# dig_usb.net
KiCad netlist of a schematic drawn in EAGLE
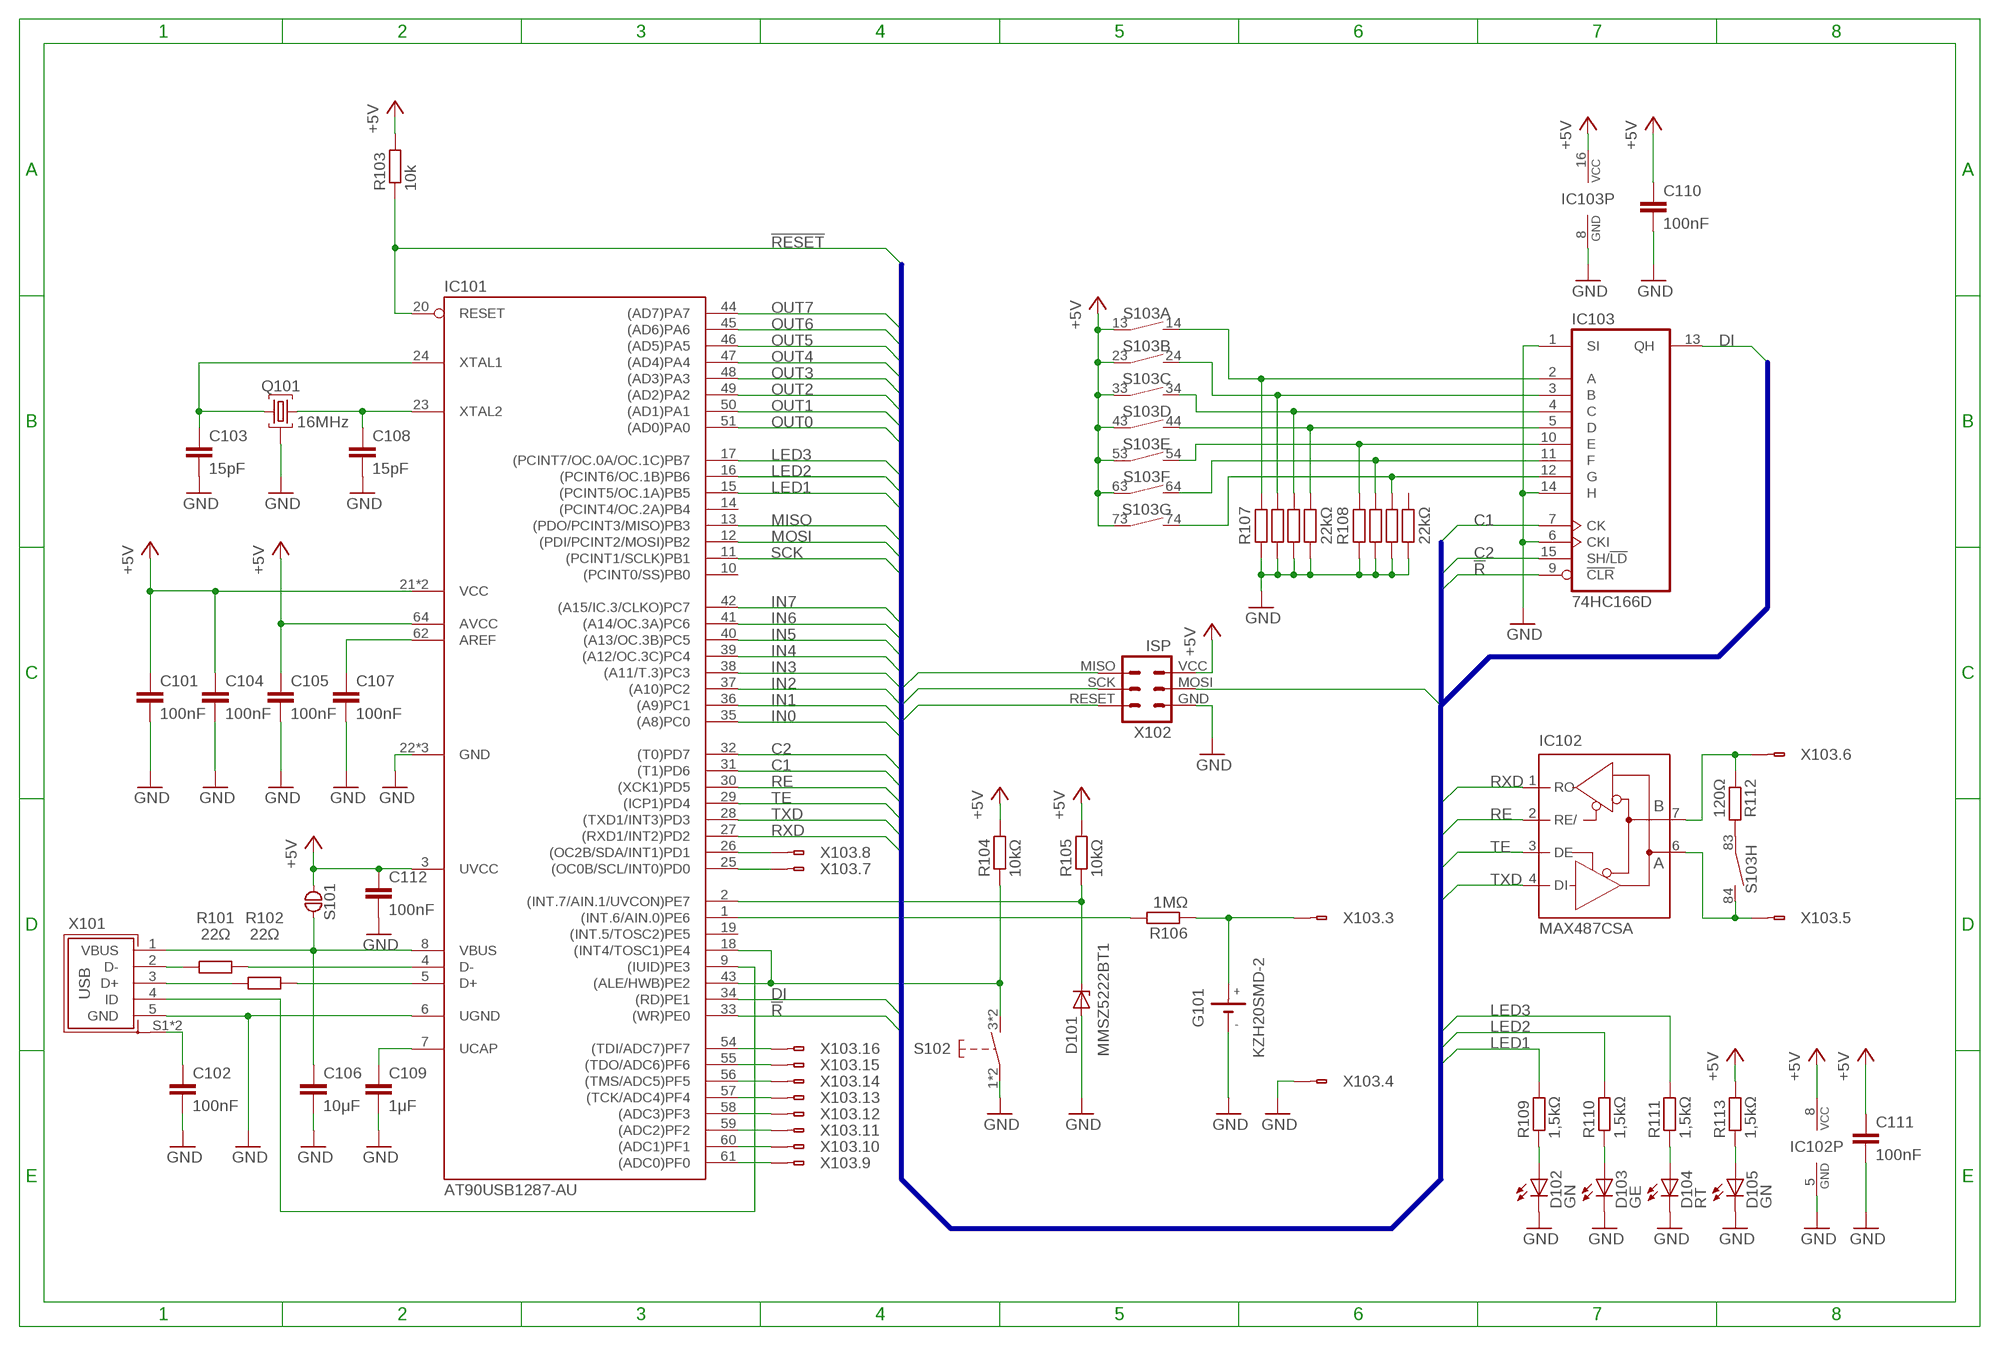
[diagram p0: schematic, sheet 1]
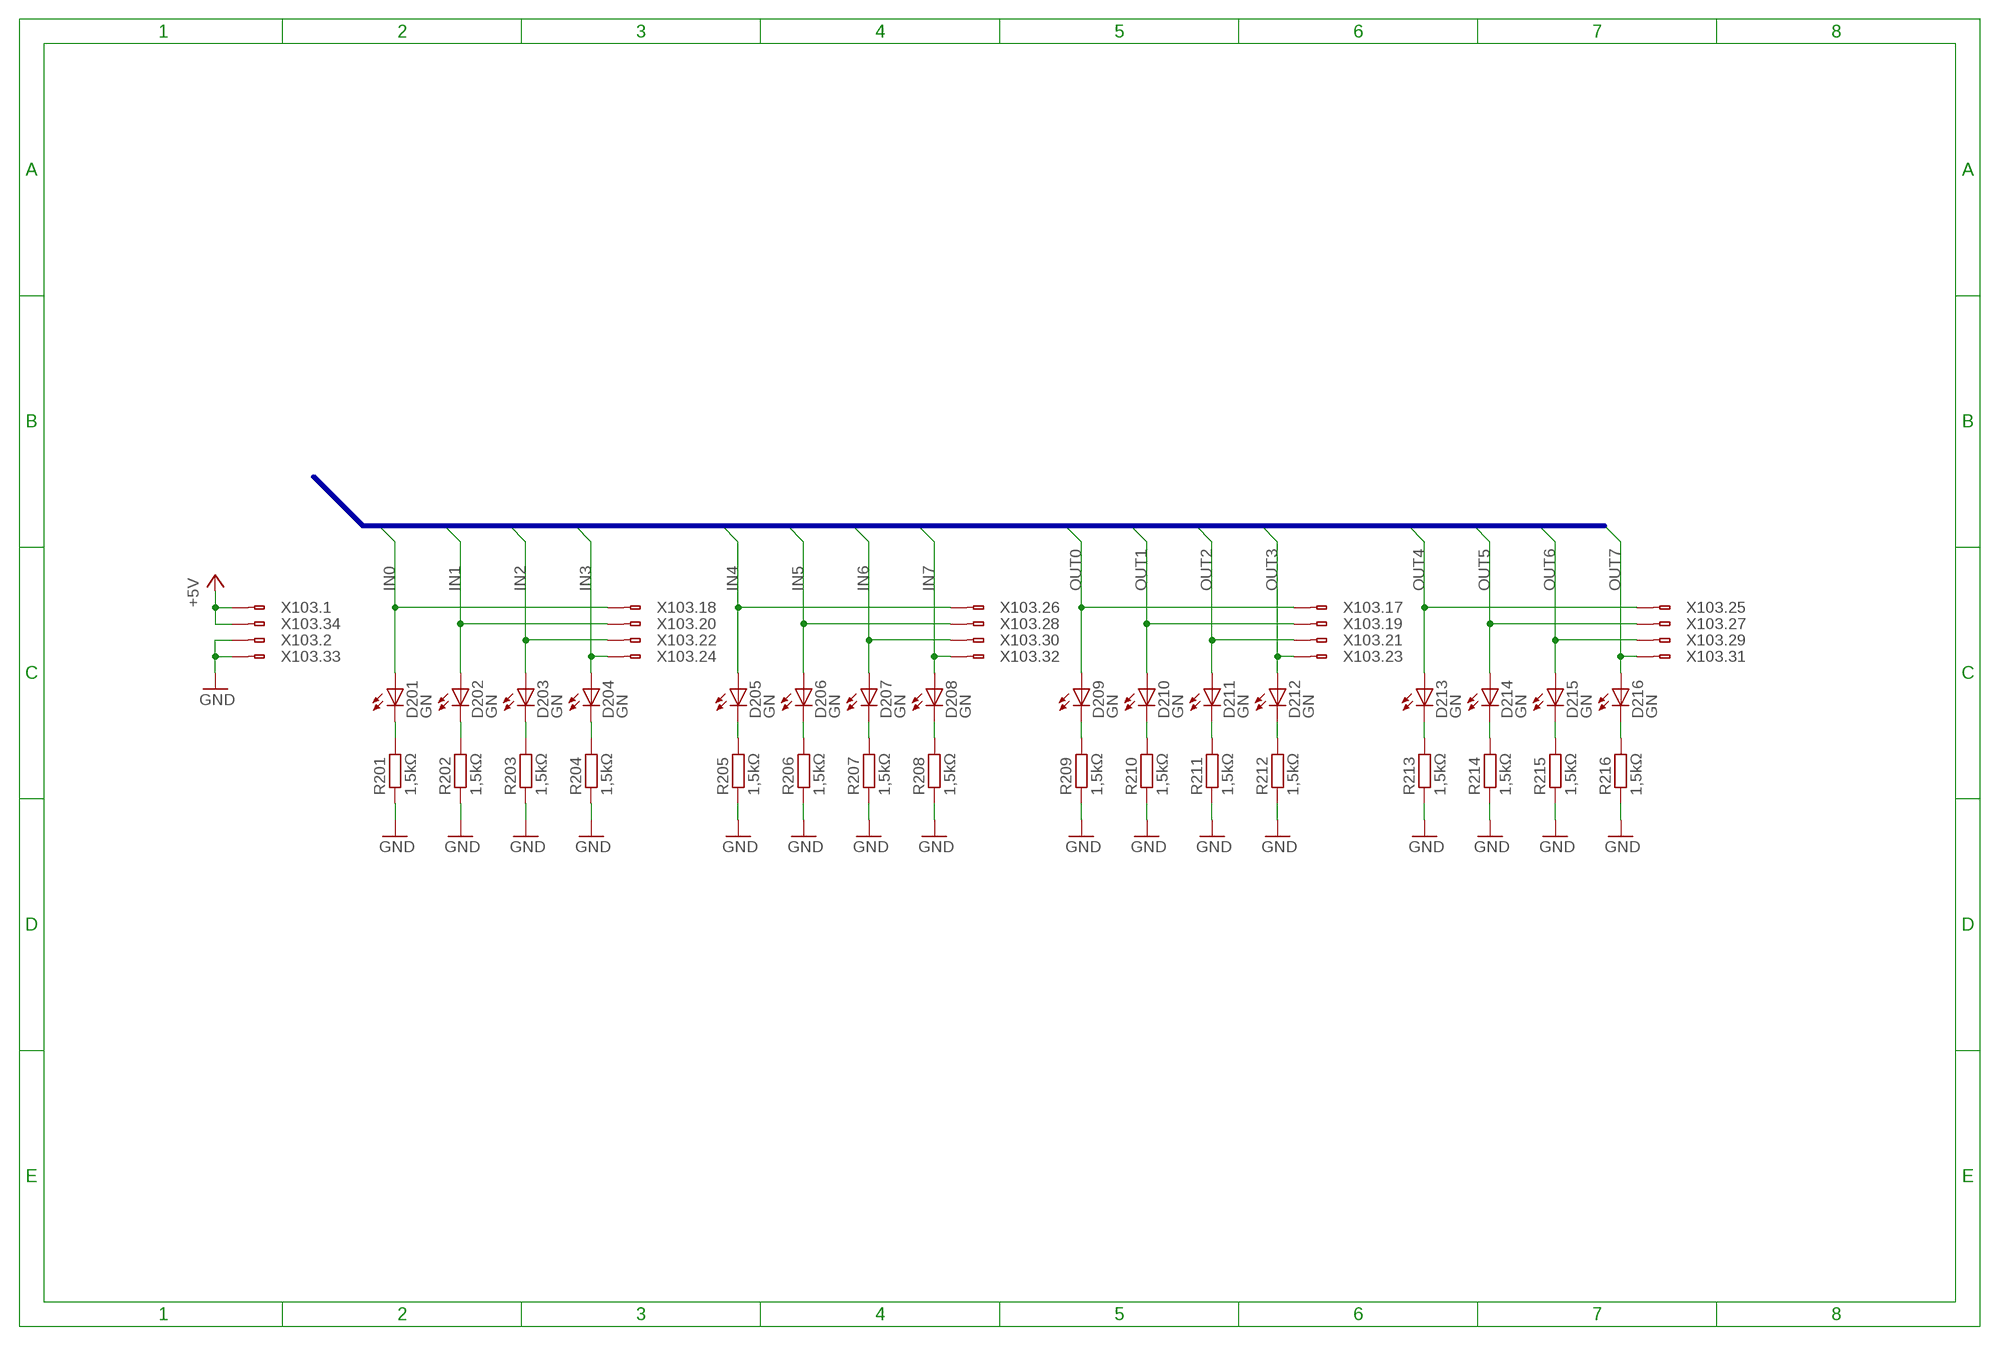
[diagram p1: schematic, sheet 2]
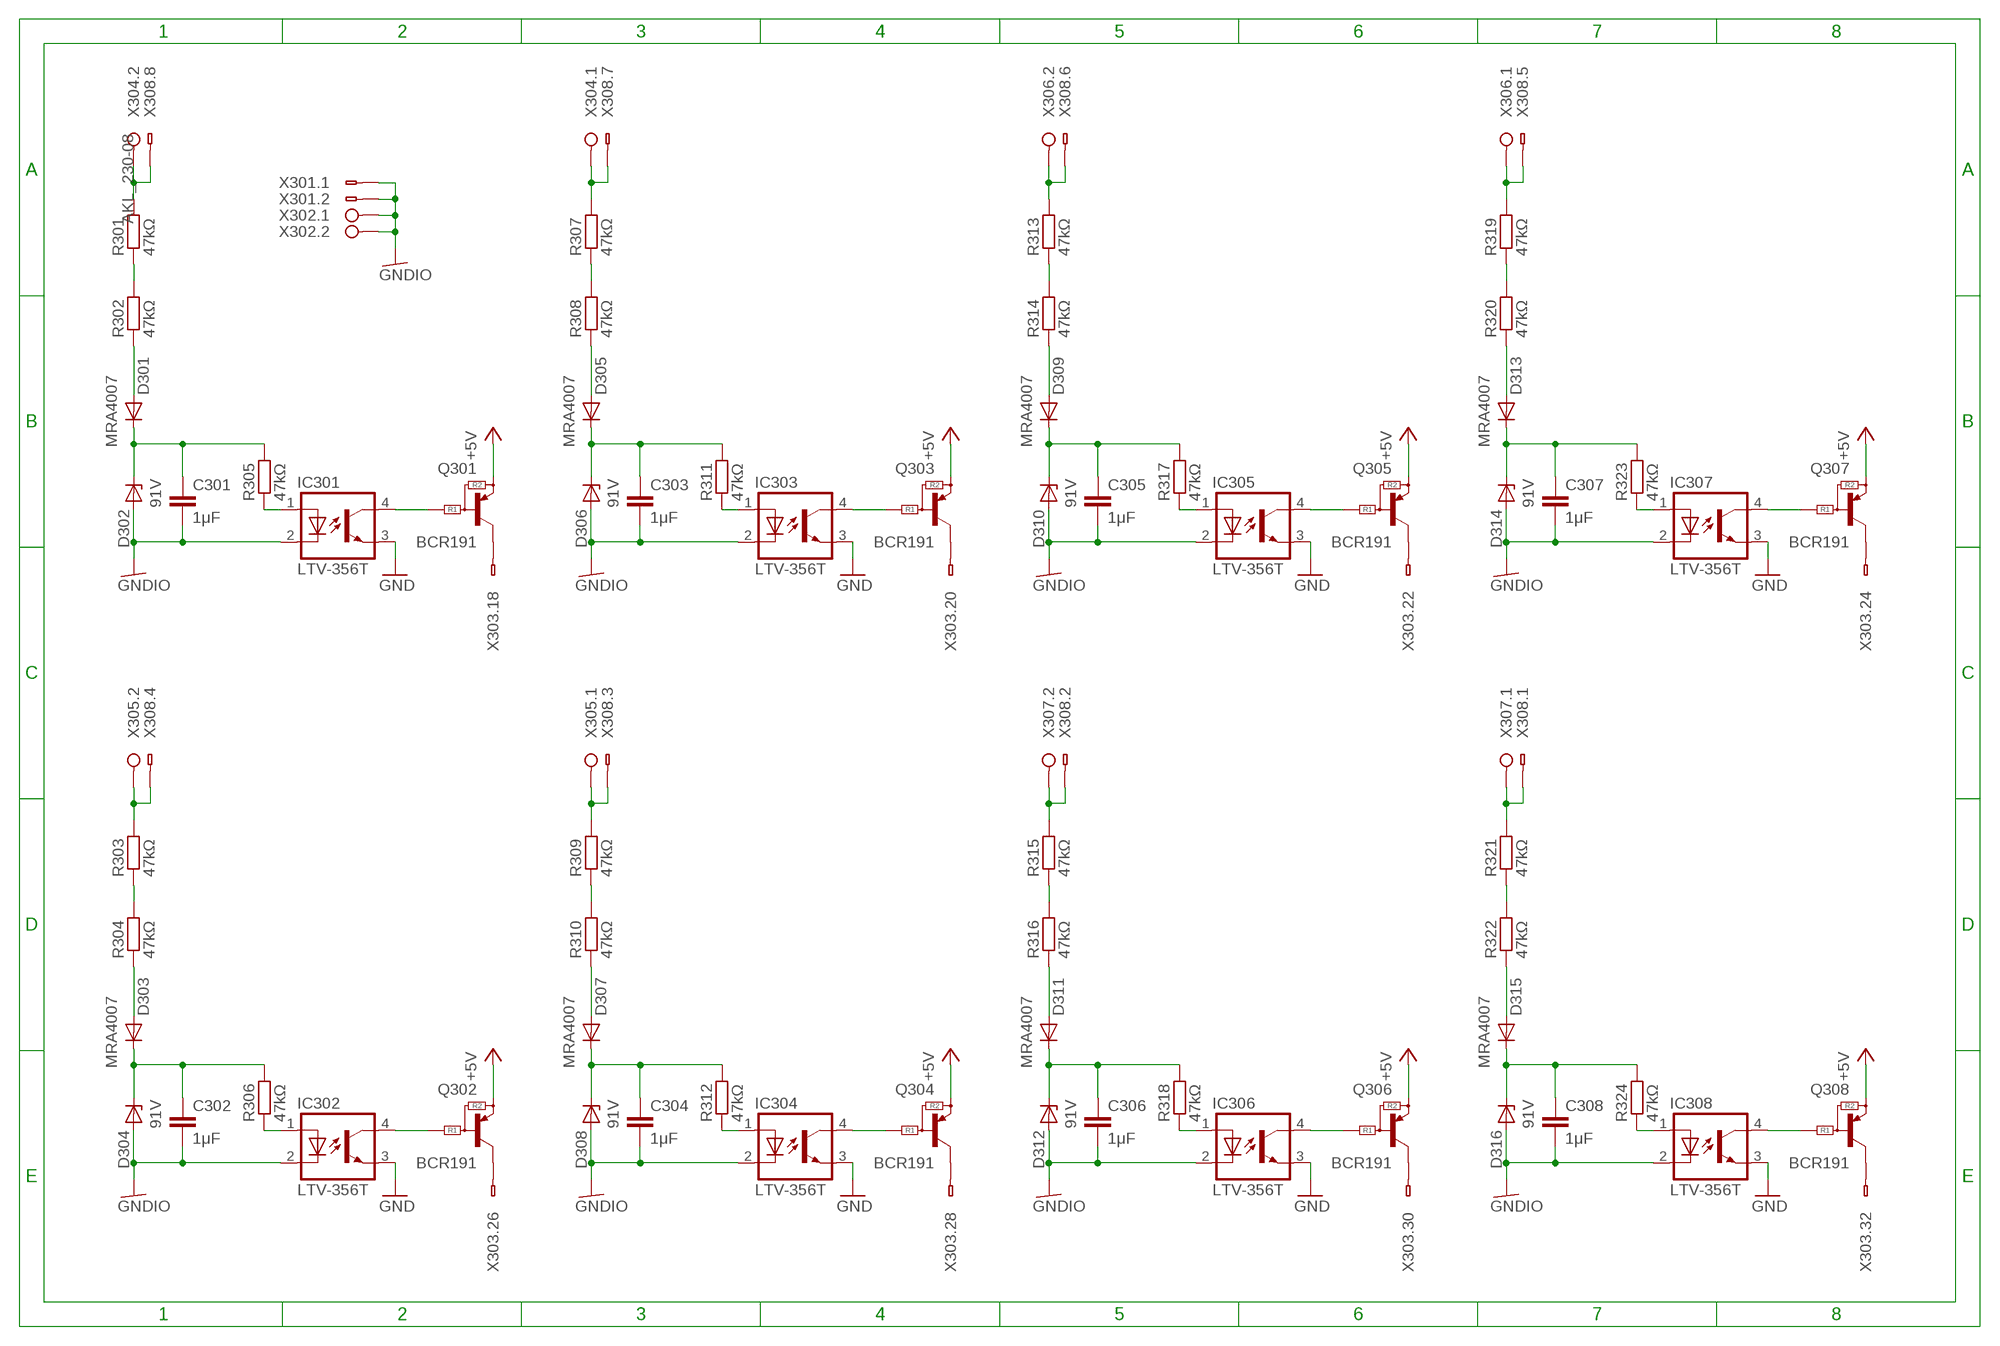
[diagram p2: schematic, sheet 3]
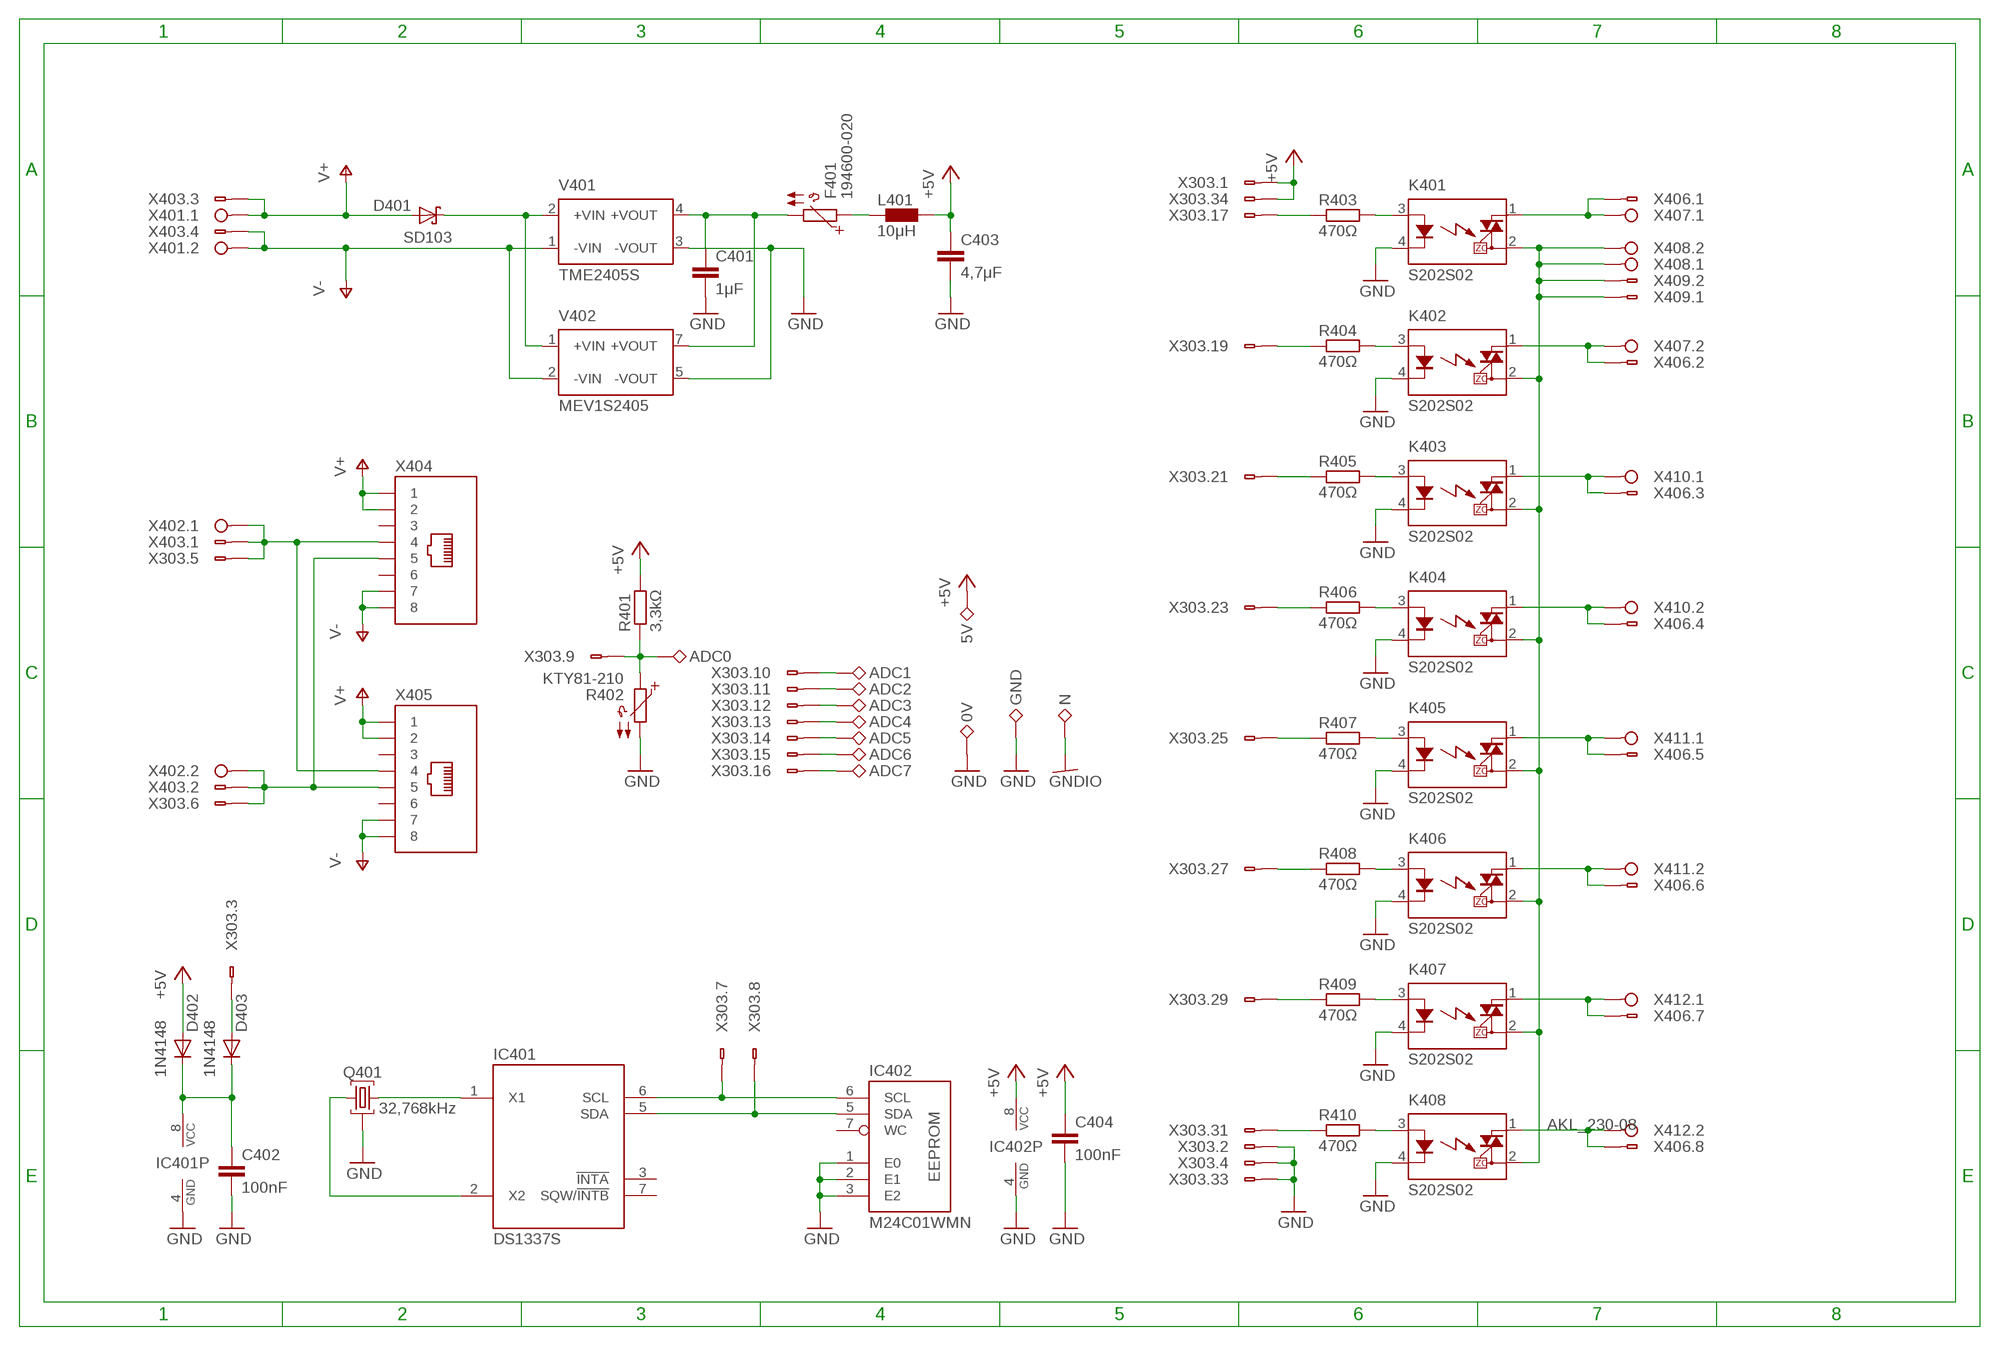
[diagram p3: schematic, sheet 4]

(export (version "E")
  (design (tool "Eeschema 10.0.6"))
  (components
    (comp (ref "C301")
      (value "1μF")
      (footprint "eagle-import:CHIP_1206")
      (libsource (lib "eagle-import") (part "C_1206"))
    )
    (comp (ref "C302")
      (value "1μF")
      (footprint "eagle-import:CHIP_1206")
      (libsource (lib "eagle-import") (part "C_1206"))
    )
    (comp (ref "C303")
      (value "1μF")
      (footprint "eagle-import:CHIP_1206")
      (libsource (lib "eagle-import") (part "C_1206"))
    )
    (comp (ref "C304")
      (value "1μF")
      (footprint "eagle-import:CHIP_1206")
      (libsource (lib "eagle-import") (part "C_1206"))
    )
    (comp (ref "C305")
      (value "1μF")
      (footprint "eagle-import:CHIP_1206")
      (libsource (lib "eagle-import") (part "C_1206"))
    )
    (comp (ref "C306")
      (value "1μF")
      (footprint "eagle-import:CHIP_1206")
      (libsource (lib "eagle-import") (part "C_1206"))
    )
    (comp (ref "C307")
      (value "1μF")
      (footprint "eagle-import:CHIP_1206")
      (libsource (lib "eagle-import") (part "C_1206"))
    )
    (comp (ref "C308")
      (value "1μF")
      (footprint "eagle-import:CHIP_1206")
      (libsource (lib "eagle-import") (part "C_1206"))
    )
    (comp (ref "D301")
      (value "MRA4007")
      (footprint "eagle-import:DO214AC")
      (libsource (lib "eagle-import") (part "DIODE-DO214AC"))
    )
    (comp (ref "D302")
      (value "91V")
      (footprint "eagle-import:SOD123")
      (libsource (lib "eagle-import") (part "Z-DIODE-SOD123"))
    )
    (comp (ref "D303")
      (value "MRA4007")
      (footprint "eagle-import:DO214AC")
      (libsource (lib "eagle-import") (part "DIODE-DO214AC"))
    )
    (comp (ref "D304")
      (value "91V")
      (footprint "eagle-import:SOD123")
      (libsource (lib "eagle-import") (part "Z-DIODE-SOD123"))
    )
    (comp (ref "D305")
      (value "MRA4007")
      (footprint "eagle-import:DO214AC")
      (libsource (lib "eagle-import") (part "DIODE-DO214AC"))
    )
    (comp (ref "D306")
      (value "91V")
      (footprint "eagle-import:SOD123")
      (libsource (lib "eagle-import") (part "Z-DIODE-SOD123"))
    )
    (comp (ref "D307")
      (value "MRA4007")
      (footprint "eagle-import:DO214AC")
      (libsource (lib "eagle-import") (part "DIODE-DO214AC"))
    )
    (comp (ref "D308")
      (value "91V")
      (footprint "eagle-import:SOD123")
      (libsource (lib "eagle-import") (part "Z-DIODE-SOD123"))
    )
    (comp (ref "D309")
      (value "MRA4007")
      (footprint "eagle-import:DO214AC")
      (libsource (lib "eagle-import") (part "DIODE-DO214AC"))
    )
    (comp (ref "D310")
      (value "91V")
      (footprint "eagle-import:SOD123")
      (libsource (lib "eagle-import") (part "Z-DIODE-SOD123"))
    )
    (comp (ref "D311")
      (value "MRA4007")
      (footprint "eagle-import:DO214AC")
      (libsource (lib "eagle-import") (part "DIODE-DO214AC"))
    )
    (comp (ref "D312")
      (value "91V")
      (footprint "eagle-import:SOD123")
      (libsource (lib "eagle-import") (part "Z-DIODE-SOD123"))
    )
    (comp (ref "D313")
      (value "MRA4007")
      (footprint "eagle-import:DO214AC")
      (libsource (lib "eagle-import") (part "DIODE-DO214AC"))
    )
    (comp (ref "D314")
      (value "91V")
      (footprint "eagle-import:SOD123")
      (libsource (lib "eagle-import") (part "Z-DIODE-SOD123"))
    )
    (comp (ref "D315")
      (value "MRA4007")
      (footprint "eagle-import:DO214AC")
      (libsource (lib "eagle-import") (part "DIODE-DO214AC"))
    )
    (comp (ref "D316")
      (value "91V")
      (footprint "eagle-import:SOD123")
      (libsource (lib "eagle-import") (part "Z-DIODE-SOD123"))
    )
    (comp (ref "IC301")
      (value "LTV-356T")
      (footprint "eagle-import:SOP04_254")
      (libsource (lib "eagle-import") (part "LTV-356T"))
    )
    (comp (ref "IC302")
      (value "LTV-356T")
      (footprint "eagle-import:SOP04_254")
      (libsource (lib "eagle-import") (part "LTV-356T"))
    )
    (comp (ref "IC303")
      (value "LTV-356T")
      (footprint "eagle-import:SOP04_254")
      (libsource (lib "eagle-import") (part "LTV-356T"))
    )
    (comp (ref "IC304")
      (value "LTV-356T")
      (footprint "eagle-import:SOP04_254")
      (libsource (lib "eagle-import") (part "LTV-356T"))
    )
    (comp (ref "IC305")
      (value "LTV-356T")
      (footprint "eagle-import:SOP04_254")
      (libsource (lib "eagle-import") (part "LTV-356T"))
    )
    (comp (ref "IC306")
      (value "LTV-356T")
      (footprint "eagle-import:SOP04_254")
      (libsource (lib "eagle-import") (part "LTV-356T"))
    )
    (comp (ref "IC307")
      (value "LTV-356T")
      (footprint "eagle-import:SOP04_254")
      (libsource (lib "eagle-import") (part "LTV-356T"))
    )
    (comp (ref "IC308")
      (value "LTV-356T")
      (footprint "eagle-import:SOP04_254")
      (libsource (lib "eagle-import") (part "LTV-356T"))
    )
    (comp (ref "Q301")
      (value "BCR191")
      (footprint "eagle-import:SOT23")
      (libsource (lib "eagle-import") (part "PNP2R-SOT23-BEC"))
    )
    (comp (ref "Q302")
      (value "BCR191")
      (footprint "eagle-import:SOT23")
      (libsource (lib "eagle-import") (part "PNP2R-SOT23-BEC"))
    )
    (comp (ref "Q303")
      (value "BCR191")
      (footprint "eagle-import:SOT23")
      (libsource (lib "eagle-import") (part "PNP2R-SOT23-BEC"))
    )
    (comp (ref "Q304")
      (value "BCR191")
      (footprint "eagle-import:SOT23")
      (libsource (lib "eagle-import") (part "PNP2R-SOT23-BEC"))
    )
    (comp (ref "Q305")
      (value "BCR191")
      (footprint "eagle-import:SOT23")
      (libsource (lib "eagle-import") (part "PNP2R-SOT23-BEC"))
    )
    (comp (ref "Q306")
      (value "BCR191")
      (footprint "eagle-import:SOT23")
      (libsource (lib "eagle-import") (part "PNP2R-SOT23-BEC"))
    )
    (comp (ref "Q307")
      (value "BCR191")
      (footprint "eagle-import:SOT23")
      (libsource (lib "eagle-import") (part "PNP2R-SOT23-BEC"))
    )
    (comp (ref "Q308")
      (value "BCR191")
      (footprint "eagle-import:SOT23")
      (libsource (lib "eagle-import") (part "PNP2R-SOT23-BEC"))
    )
    (comp (ref "R301")
      (value "47kΩ")
      (footprint "eagle-import:CHIP_1206")
      (libsource (lib "eagle-import") (part "R_1206"))
    )
    (comp (ref "R302")
      (value "47kΩ")
      (footprint "eagle-import:CHIP_1206")
      (libsource (lib "eagle-import") (part "R_1206"))
    )
    (comp (ref "R303")
      (value "47kΩ")
      (footprint "eagle-import:CHIP_1206")
      (libsource (lib "eagle-import") (part "R_1206"))
    )
    (comp (ref "R304")
      (value "47kΩ")
      (footprint "eagle-import:CHIP_1206")
      (libsource (lib "eagle-import") (part "R_1206"))
    )
    (comp (ref "R305")
      (value "47kΩ")
      (footprint "eagle-import:CHIP_1206")
      (libsource (lib "eagle-import") (part "R_1206"))
    )
    (comp (ref "R306")
      (value "47kΩ")
      (footprint "eagle-import:CHIP_1206")
      (libsource (lib "eagle-import") (part "R_1206"))
    )
    (comp (ref "R307")
      (value "47kΩ")
      (footprint "eagle-import:CHIP_1206")
      (libsource (lib "eagle-import") (part "R_1206"))
    )
    (comp (ref "R308")
      (value "47kΩ")
      (footprint "eagle-import:CHIP_1206")
      (libsource (lib "eagle-import") (part "R_1206"))
    )
    (comp (ref "R309")
      (value "47kΩ")
      (footprint "eagle-import:CHIP_1206")
      (libsource (lib "eagle-import") (part "R_1206"))
    )
    (comp (ref "R310")
      (value "47kΩ")
      (footprint "eagle-import:CHIP_1206")
      (libsource (lib "eagle-import") (part "R_1206"))
    )
    (comp (ref "R311")
      (value "47kΩ")
      (footprint "eagle-import:CHIP_1206")
      (libsource (lib "eagle-import") (part "R_1206"))
    )
    (comp (ref "R312")
      (value "47kΩ")
      (footprint "eagle-import:CHIP_1206")
      (libsource (lib "eagle-import") (part "R_1206"))
    )
    (comp (ref "R313")
      (value "47kΩ")
      (footprint "eagle-import:CHIP_1206")
      (libsource (lib "eagle-import") (part "R_1206"))
    )
    (comp (ref "R314")
      (value "47kΩ")
      (footprint "eagle-import:CHIP_1206")
      (libsource (lib "eagle-import") (part "R_1206"))
    )
    (comp (ref "R315")
      (value "47kΩ")
      (footprint "eagle-import:CHIP_1206")
      (libsource (lib "eagle-import") (part "R_1206"))
    )
    (comp (ref "R316")
      (value "47kΩ")
      (footprint "eagle-import:CHIP_1206")
      (libsource (lib "eagle-import") (part "R_1206"))
    )
    (comp (ref "R317")
      (value "47kΩ")
      (footprint "eagle-import:CHIP_1206")
      (libsource (lib "eagle-import") (part "R_1206"))
    )
    (comp (ref "R318")
      (value "47kΩ")
      (footprint "eagle-import:CHIP_1206")
      (libsource (lib "eagle-import") (part "R_1206"))
    )
    (comp (ref "R319")
      (value "47kΩ")
      (footprint "eagle-import:CHIP_1206")
      (libsource (lib "eagle-import") (part "R_1206"))
    )
    (comp (ref "R320")
      (value "47kΩ")
      (footprint "eagle-import:CHIP_1206")
      (libsource (lib "eagle-import") (part "R_1206"))
    )
    (comp (ref "R321")
      (value "47kΩ")
      (footprint "eagle-import:CHIP_1206")
      (libsource (lib "eagle-import") (part "R_1206"))
    )
    (comp (ref "R322")
      (value "47kΩ")
      (footprint "eagle-import:CHIP_1206")
      (libsource (lib "eagle-import") (part "R_1206"))
    )
    (comp (ref "R323")
      (value "47kΩ")
      (footprint "eagle-import:CHIP_1206")
      (libsource (lib "eagle-import") (part "R_1206"))
    )
    (comp (ref "R324")
      (value "47kΩ")
      (footprint "eagle-import:CHIP_1206")
      (libsource (lib "eagle-import") (part "R_1206"))
    )
    (comp (ref "X301")
      (value "AKL_230-02")
      (footprint "eagle-import:AKL_230-02")
      (libsource (lib "eagle-import") (part "AKL_230-02"))
    )
    (comp (ref "X302")
      (value "RIA-73-02")
      (footprint "eagle-import:RIA-73-02")
      (libsource (lib "eagle-import") (part "RIA-73-02"))
    )
    (comp (ref "X303")
      (value "WS34V")
      (footprint "eagle-import:WS34V")
      (libsource (lib "eagle-import") (part "WS34V"))
    )
    (comp (ref "X304")
      (value "RIA-73-02")
      (footprint "eagle-import:RIA-73-02")
      (libsource (lib "eagle-import") (part "RIA-73-02"))
    )
    (comp (ref "X305")
      (value "RIA-73-02")
      (footprint "eagle-import:RIA-73-02")
      (libsource (lib "eagle-import") (part "RIA-73-02"))
    )
    (comp (ref "X306")
      (value "RIA-73-02")
      (footprint "eagle-import:RIA-73-02")
      (libsource (lib "eagle-import") (part "RIA-73-02"))
    )
    (comp (ref "X307")
      (value "RIA-73-02")
      (footprint "eagle-import:RIA-73-02")
      (libsource (lib "eagle-import") (part "RIA-73-02"))
    )
    (comp (ref "X308")
      (value "AKL_230-08")
      (footprint "eagle-import:AKL_230-08")
      (libsource (lib "eagle-import") (part "AKL_230-08"))
    )
    (comp (ref "C101")
      (value "100nF")
      (footprint "eagle-import:CHIP_0603")
      (libsource (lib "eagle-import") (part "C_0603"))
    )
    (comp (ref "C102")
      (value "100nF")
      (footprint "eagle-import:CHIP_0805")
      (libsource (lib "eagle-import") (part "C_0805"))
    )
    (comp (ref "C103")
      (value "15pF")
      (footprint "eagle-import:CHIP_0805")
      (libsource (lib "eagle-import") (part "C_0805"))
    )
    (comp (ref "C104")
      (value "100nF")
      (footprint "eagle-import:CHIP_0603")
      (libsource (lib "eagle-import") (part "C_0603"))
    )
    (comp (ref "C105")
      (value "100nF")
      (footprint "eagle-import:CHIP_0603")
      (libsource (lib "eagle-import") (part "C_0603"))
    )
    (comp (ref "C106")
      (value "10μF")
      (footprint "eagle-import:CHIP_0805")
      (libsource (lib "eagle-import") (part "C_0805"))
    )
    (comp (ref "C107")
      (value "100nF")
      (footprint "eagle-import:CHIP_0603")
      (libsource (lib "eagle-import") (part "C_0603"))
    )
    (comp (ref "C108")
      (value "15pF")
      (footprint "eagle-import:CHIP_0805")
      (libsource (lib "eagle-import") (part "C_0805"))
    )
    (comp (ref "C109")
      (value "1μF")
      (footprint "eagle-import:CHIP_0805")
      (libsource (lib "eagle-import") (part "C_0805"))
    )
    (comp (ref "C110")
      (value "100nF")
      (footprint "eagle-import:CHIP_0603")
      (libsource (lib "eagle-import") (part "C_0603"))
    )
    (comp (ref "C111")
      (value "100nF")
      (footprint "eagle-import:CHIP_0603")
      (libsource (lib "eagle-import") (part "C_0603"))
    )
    (comp (ref "C112")
      (value "100nF")
      (footprint "eagle-import:CHIP_0603")
      (libsource (lib "eagle-import") (part "C_0603"))
    )
    (comp (ref "D101")
      (value "MMSZ5222BT1")
      (footprint "eagle-import:SOD123")
      (libsource (lib "eagle-import") (part "Z-DIODE-SOD123"))
    )
    (comp (ref "D102")
      (value "GN")
      (footprint "eagle-import:CHIP_0805")
      (libsource (lib "eagle-import") (part "LED_0805"))
    )
    (comp (ref "D103")
      (value "GE")
      (footprint "eagle-import:CHIP_0805")
      (libsource (lib "eagle-import") (part "LED_0805"))
    )
    (comp (ref "D104")
      (value "RT")
      (footprint "eagle-import:CHIP_0805")
      (libsource (lib "eagle-import") (part "LED_0805"))
    )
    (comp (ref "D105")
      (value "GN")
      (footprint "eagle-import:CHIP_0805")
      (libsource (lib "eagle-import") (part "LED_0805"))
    )
    (comp (ref "G101")
      (value "KZH20SMD-2")
      (footprint "eagle-import:KHZ20SMD-2")
      (libsource (lib "eagle-import") (part "KZH20SMD-2"))
    )
    (comp (ref "IC101")
      (value "AT90USB1287-AU")
      (footprint "eagle-import:QFP64_08")
      (libsource (lib "eagle-import") (part "AT90USB1287-AU"))
    )
    (comp (ref "IC102")
      (value "MAX487CSA")
      (footprint "eagle-import:SOP08_127")
      (libsource (lib "eagle-import") (part "MAX48CSA7"))
    )
    (comp (ref "IC103")
      (value "74HC166D")
      (footprint "eagle-import:SOP16_127")
      (libsource (lib "eagle-import") (part "74166DHC"))
    )
    (comp (ref "Q101")
      (value "16MHz")
      (footprint "eagle-import:X22")
      (libsource (lib "eagle-import") (part "QM_X22"))
    )
    (comp (ref "R101")
      (value "22Ω")
      (footprint "eagle-import:CHIP_0805")
      (libsource (lib "eagle-import") (part "R_0805"))
    )
    (comp (ref "R102")
      (value "22Ω")
      (footprint "eagle-import:CHIP_0805")
      (libsource (lib "eagle-import") (part "R_0805"))
    )
    (comp (ref "R103")
      (value "10k")
      (footprint "eagle-import:CHIP_0805")
      (libsource (lib "eagle-import") (part "R_0805"))
    )
    (comp (ref "R104")
      (value "10kΩ")
      (footprint "eagle-import:CHIP_0805")
      (libsource (lib "eagle-import") (part "R_0805"))
    )
    (comp (ref "R105")
      (value "10kΩ")
      (footprint "eagle-import:CHIP_0805")
      (libsource (lib "eagle-import") (part "R_0805"))
    )
    (comp (ref "R106")
      (value "1MΩ")
      (footprint "eagle-import:CHIP_0805")
      (libsource (lib "eagle-import") (part "R_0805"))
    )
    (comp (ref "R107")
      (value "22kΩ")
      (footprint "eagle-import:1206")
      (libsource (lib "eagle-import") (part "EXB-38V"))
    )
    (comp (ref "R108")
      (value "22kΩ")
      (footprint "eagle-import:1206")
      (libsource (lib "eagle-import") (part "EXB-38V"))
    )
    (comp (ref "R109")
      (value "1,5kΩ")
      (footprint "eagle-import:CHIP_0805")
      (libsource (lib "eagle-import") (part "R_0805"))
    )
    (comp (ref "R110")
      (value "1,5kΩ")
      (footprint "eagle-import:CHIP_0805")
      (libsource (lib "eagle-import") (part "R_0805"))
    )
    (comp (ref "R111")
      (value "1,5kΩ")
      (footprint "eagle-import:CHIP_0805")
      (libsource (lib "eagle-import") (part "R_0805"))
    )
    (comp (ref "R112")
      (value "120Ω")
      (footprint "eagle-import:CHIP_0805")
      (libsource (lib "eagle-import") (part "R_0805"))
    )
    (comp (ref "R113")
      (value "1,5kΩ")
      (footprint "eagle-import:CHIP_0805")
      (libsource (lib "eagle-import") (part "R_0805"))
    )
    (comp (ref "S101")
      (value "JUMPER")
      (footprint "eagle-import:JUMPER2")
      (libsource (lib "eagle-import") (part "JUMPER"))
    )
    (comp (ref "S102")
      (value "KURZHUBS1")
      (footprint "eagle-import:SCHURTER1301")
      (libsource (lib "eagle-import") (part "KURZHUBS1"))
    )
    (comp (ref "S103")
      (value "DP08D")
      (footprint "eagle-import:DIP08_SMD")
      (libsource (lib "eagle-import") (part "DP08D"))
    )
    (comp (ref "X101")
      (value "USB-MINI-V")
      (footprint "eagle-import:WE651005136421")
      (libsource (lib "eagle-import") (part "USB-MINI-V"))
    )
    (comp (ref "X102")
      (value "ISP")
      (footprint "eagle-import:ML6")
      (libsource (lib "eagle-import") (part "AVR_ISP6"))
    )
    (comp (ref "X103")
      (value "WS34V")
      (footprint "eagle-import:WS34V")
      (libsource (lib "eagle-import") (part "WS34V"))
    )
    (comp (ref "0V")
      (value "TEST_VIA_08")
      (footprint "eagle-import:VIA08")
      (libsource (lib "eagle-import") (part "TEST_VIA_08"))
    )
    (comp (ref "5V")
      (value "TEST_VIA_08")
      (footprint "eagle-import:VIA08")
      (libsource (lib "eagle-import") (part "TEST_VIA_08"))
    )
    (comp (ref "ADC0")
      (value "TEST_PAD_SMALL")
      (footprint "eagle-import:PADS")
      (libsource (lib "eagle-import") (part "TEST_PAD_SMALL"))
    )
    (comp (ref "ADC1")
      (value "TEST_PAD_SMALL")
      (footprint "eagle-import:PADS")
      (libsource (lib "eagle-import") (part "TEST_PAD_SMALL"))
    )
    (comp (ref "ADC2")
      (value "TEST_PAD_SMALL")
      (footprint "eagle-import:PADS")
      (libsource (lib "eagle-import") (part "TEST_PAD_SMALL"))
    )
    (comp (ref "ADC3")
      (value "TEST_PAD_SMALL")
      (footprint "eagle-import:PADS")
      (libsource (lib "eagle-import") (part "TEST_PAD_SMALL"))
    )
    (comp (ref "ADC4")
      (value "TEST_PAD_SMALL")
      (footprint "eagle-import:PADS")
      (libsource (lib "eagle-import") (part "TEST_PAD_SMALL"))
    )
    (comp (ref "ADC5")
      (value "TEST_PAD_SMALL")
      (footprint "eagle-import:PADS")
      (libsource (lib "eagle-import") (part "TEST_PAD_SMALL"))
    )
    (comp (ref "ADC6")
      (value "TEST_PAD_SMALL")
      (footprint "eagle-import:PADS")
      (libsource (lib "eagle-import") (part "TEST_PAD_SMALL"))
    )
    (comp (ref "ADC7")
      (value "TEST_PAD_SMALL")
      (footprint "eagle-import:PADS")
      (libsource (lib "eagle-import") (part "TEST_PAD_SMALL"))
    )
    (comp (ref "C401")
      (value "1μF")
      (footprint "eagle-import:CHIP_0805")
      (libsource (lib "eagle-import") (part "C_0805"))
    )
    (comp (ref "C402")
      (value "100nF")
      (footprint "eagle-import:CHIP_0603")
      (libsource (lib "eagle-import") (part "C_0603"))
    )
    (comp (ref "C403")
      (value "4,7μF")
      (footprint "eagle-import:CHIP_0805")
      (libsource (lib "eagle-import") (part "C_0805"))
    )
    (comp (ref "C404")
      (value "100nF")
      (footprint "eagle-import:CHIP_0603")
      (libsource (lib "eagle-import") (part "C_0603"))
    )
    (comp (ref "D401")
      (value "SD103")
      (footprint "eagle-import:SOD123")
      (libsource (lib "eagle-import") (part "SHOTKY-DIODE-SOD123"))
    )
    (comp (ref "D402")
      (value "1N4148")
      (footprint "eagle-import:SOD123")
      (libsource (lib "eagle-import") (part "DIODE-SOD123"))
    )
    (comp (ref "D403")
      (value "1N4148")
      (footprint "eagle-import:SOD123")
      (libsource (lib "eagle-import") (part "DIODE-SOD123"))
    )
    (comp (ref "F401")
      (value "194600-020")
      (footprint "eagle-import:CHIP_1812")
      (libsource (lib "eagle-import") (part "194600-020"))
    )
    (comp (ref "GND")
      (value "TEST_VIA_08")
      (footprint "eagle-import:VIA08")
      (libsource (lib "eagle-import") (part "TEST_VIA_08"))
    )
    (comp (ref "IC401")
      (value "DS1337S")
      (footprint "eagle-import:SOP08_127")
      (libsource (lib "eagle-import") (part "DS1337S"))
    )
    (comp (ref "IC402")
      (value "M24C01WMN")
      (footprint "eagle-import:SOP08_127")
      (libsource (lib "eagle-import") (part "M24C01MNW"))
    )
    (comp (ref "K401")
      (value "S202S02")
      (footprint "eagle-import:SIP4")
      (libsource (lib "eagle-import") (part "S02S022"))
    )
    (comp (ref "K402")
      (value "S202S02")
      (footprint "eagle-import:SIP4")
      (libsource (lib "eagle-import") (part "S02S022"))
    )
    (comp (ref "K403")
      (value "S202S02")
      (footprint "eagle-import:SIP4")
      (libsource (lib "eagle-import") (part "S02S022"))
    )
    (comp (ref "K404")
      (value "S202S02")
      (footprint "eagle-import:SIP4")
      (libsource (lib "eagle-import") (part "S02S022"))
    )
    (comp (ref "K405")
      (value "S202S02")
      (footprint "eagle-import:SIP4")
      (libsource (lib "eagle-import") (part "S02S022"))
    )
    (comp (ref "K406")
      (value "S202S02")
      (footprint "eagle-import:SIP4")
      (libsource (lib "eagle-import") (part "S02S022"))
    )
    (comp (ref "K407")
      (value "S202S02")
      (footprint "eagle-import:SIP4")
      (libsource (lib "eagle-import") (part "S02S022"))
    )
    (comp (ref "K408")
      (value "S202S02")
      (footprint "eagle-import:SIP4")
      (libsource (lib "eagle-import") (part "S02S022"))
    )
    (comp (ref "L401")
      (value "10μH")
      (footprint "eagle-import:1812AF")
      (libsource (lib "eagle-import") (part "L_1812AF"))
    )
    (comp (ref "N")
      (value "TEST_VIA_08")
      (footprint "eagle-import:VIA08")
      (libsource (lib "eagle-import") (part "TEST_VIA_08"))
    )
    (comp (ref "Q401")
      (value "32,768kHz")
      (footprint "eagle-import:MS1V-T1K")
      (libsource (lib "eagle-import") (part "QM_MS1V-T1K"))
    )
    (comp (ref "R401")
      (value "3,3kΩ")
      (footprint "eagle-import:CHIP_0805")
      (libsource (lib "eagle-import") (part "R_0805"))
    )
    (comp (ref "R402")
      (value "KTY81-210")
      (footprint "eagle-import:TO92")
      (libsource (lib "eagle-import") (part "KTY81-210"))
    )
    (comp (ref "R403")
      (value "470Ω")
      (footprint "eagle-import:CHIP_0805")
      (libsource (lib "eagle-import") (part "R_0805"))
    )
    (comp (ref "R404")
      (value "470Ω")
      (footprint "eagle-import:CHIP_0805")
      (libsource (lib "eagle-import") (part "R_0805"))
    )
    (comp (ref "R405")
      (value "470Ω")
      (footprint "eagle-import:CHIP_0805")
      (libsource (lib "eagle-import") (part "R_0805"))
    )
    (comp (ref "R406")
      (value "470Ω")
      (footprint "eagle-import:CHIP_0805")
      (libsource (lib "eagle-import") (part "R_0805"))
    )
    (comp (ref "R407")
      (value "470Ω")
      (footprint "eagle-import:CHIP_0805")
      (libsource (lib "eagle-import") (part "R_0805"))
    )
    (comp (ref "R408")
      (value "470Ω")
      (footprint "eagle-import:CHIP_0805")
      (libsource (lib "eagle-import") (part "R_0805"))
    )
    (comp (ref "R409")
      (value "470Ω")
      (footprint "eagle-import:CHIP_0805")
      (libsource (lib "eagle-import") (part "R_0805"))
    )
    (comp (ref "R410")
      (value "470Ω")
      (footprint "eagle-import:CHIP_0805")
      (libsource (lib "eagle-import") (part "R_0805"))
    )
    (comp (ref "V401")
      (value "TME2405S")
      (footprint "eagle-import:TME-24V")
      (fields
        (field (name "MPN") "TME 2405S")
        (field (name "MPN_1") "TME 2405S")
        (field (name "OC_FARNELL") "1007547")
        (field (name "OC_NEWARK") "51R5329")
      )
      (libsource (lib "eagle-import") (part "TME?2405S"))
    )
    (comp (ref "V402")
      (value "MEV1S2405")
      (footprint "eagle-import:MEV1S")
      (libsource (lib "eagle-import") (part "MEV1S?2405"))
    )
    (comp (ref "X401")
      (value "RIA-73-02")
      (footprint "eagle-import:RIA-73-02")
      (libsource (lib "eagle-import") (part "RIA-73-02"))
    )
    (comp (ref "X402")
      (value "RIA-73-02")
      (footprint "eagle-import:RIA-73-02")
      (libsource (lib "eagle-import") (part "RIA-73-02"))
    )
    (comp (ref "X403")
      (value "AKL_230-04")
      (footprint "eagle-import:AKL_230-04")
      (libsource (lib "eagle-import") (part "AKL_230-04"))
    )
    (comp (ref "X404")
      (value "8P8C")
      (footprint "eagle-import:C-BMJ-0102")
      (libsource (lib "eagle-import") (part "8P8C"))
    )
    (comp (ref "X405")
      (value "8P8C")
      (footprint "eagle-import:C-BMJ-0102")
      (libsource (lib "eagle-import") (part "8P8C"))
    )
    (comp (ref "X406")
      (value "AKL_230-08")
      (footprint "eagle-import:AKL_230-08")
      (libsource (lib "eagle-import") (part "AKL_230-08"))
    )
    (comp (ref "X407")
      (value "RIA-73-02")
      (footprint "eagle-import:RIA-73-02")
      (libsource (lib "eagle-import") (part "RIA-73-02"))
    )
    (comp (ref "X408")
      (value "RIA-73-02")
      (footprint "eagle-import:RIA-73-02")
      (libsource (lib "eagle-import") (part "RIA-73-02"))
    )
    (comp (ref "X409")
      (value "AKL_230-02")
      (footprint "eagle-import:AKL_230-02")
      (libsource (lib "eagle-import") (part "AKL_230-02"))
    )
    (comp (ref "X410")
      (value "RIA-73-02")
      (footprint "eagle-import:RIA-73-02")
      (libsource (lib "eagle-import") (part "RIA-73-02"))
    )
    (comp (ref "X411")
      (value "RIA-73-02")
      (footprint "eagle-import:RIA-73-02")
      (libsource (lib "eagle-import") (part "RIA-73-02"))
    )
    (comp (ref "X412")
      (value "RIA-73-02")
      (footprint "eagle-import:RIA-73-02")
      (libsource (lib "eagle-import") (part "RIA-73-02"))
    )
    (comp (ref "D201")
      (value "GN")
      (footprint "eagle-import:CHIP_0805")
      (libsource (lib "eagle-import") (part "LED_0805"))
    )
    (comp (ref "D202")
      (value "GN")
      (footprint "eagle-import:CHIP_0805")
      (libsource (lib "eagle-import") (part "LED_0805"))
    )
    (comp (ref "D203")
      (value "GN")
      (footprint "eagle-import:CHIP_0805")
      (libsource (lib "eagle-import") (part "LED_0805"))
    )
    (comp (ref "D204")
      (value "GN")
      (footprint "eagle-import:CHIP_0805")
      (libsource (lib "eagle-import") (part "LED_0805"))
    )
    (comp (ref "D205")
      (value "GN")
      (footprint "eagle-import:CHIP_0805")
      (libsource (lib "eagle-import") (part "LED_0805"))
    )
    (comp (ref "D206")
      (value "GN")
      (footprint "eagle-import:CHIP_0805")
      (libsource (lib "eagle-import") (part "LED_0805"))
    )
    (comp (ref "D207")
      (value "GN")
      (footprint "eagle-import:CHIP_0805")
      (libsource (lib "eagle-import") (part "LED_0805"))
    )
    (comp (ref "D208")
      (value "GN")
      (footprint "eagle-import:CHIP_0805")
      (libsource (lib "eagle-import") (part "LED_0805"))
    )
    (comp (ref "D209")
      (value "GN")
      (footprint "eagle-import:CHIP_0805")
      (libsource (lib "eagle-import") (part "LED_0805"))
    )
    (comp (ref "D210")
      (value "GN")
      (footprint "eagle-import:CHIP_0805")
      (libsource (lib "eagle-import") (part "LED_0805"))
    )
    (comp (ref "D211")
      (value "GN")
      (footprint "eagle-import:CHIP_0805")
      (libsource (lib "eagle-import") (part "LED_0805"))
    )
    (comp (ref "D212")
      (value "GN")
      (footprint "eagle-import:CHIP_0805")
      (libsource (lib "eagle-import") (part "LED_0805"))
    )
    (comp (ref "D213")
      (value "GN")
      (footprint "eagle-import:CHIP_0805")
      (libsource (lib "eagle-import") (part "LED_0805"))
    )
    (comp (ref "D214")
      (value "GN")
      (footprint "eagle-import:CHIP_0805")
      (libsource (lib "eagle-import") (part "LED_0805"))
    )
    (comp (ref "D215")
      (value "GN")
      (footprint "eagle-import:CHIP_0805")
      (libsource (lib "eagle-import") (part "LED_0805"))
    )
    (comp (ref "D216")
      (value "GN")
      (footprint "eagle-import:CHIP_0805")
      (libsource (lib "eagle-import") (part "LED_0805"))
    )
    (comp (ref "R201")
      (value "1,5kΩ")
      (footprint "eagle-import:CHIP_0805")
      (libsource (lib "eagle-import") (part "R_0805"))
    )
    (comp (ref "R202")
      (value "1,5kΩ")
      (footprint "eagle-import:CHIP_0805")
      (libsource (lib "eagle-import") (part "R_0805"))
    )
    (comp (ref "R203")
      (value "1,5kΩ")
      (footprint "eagle-import:CHIP_0805")
      (libsource (lib "eagle-import") (part "R_0805"))
    )
    (comp (ref "R204")
      (value "1,5kΩ")
      (footprint "eagle-import:CHIP_0805")
      (libsource (lib "eagle-import") (part "R_0805"))
    )
    (comp (ref "R205")
      (value "1,5kΩ")
      (footprint "eagle-import:CHIP_0805")
      (libsource (lib "eagle-import") (part "R_0805"))
    )
    (comp (ref "R206")
      (value "1,5kΩ")
      (footprint "eagle-import:CHIP_0805")
      (libsource (lib "eagle-import") (part "R_0805"))
    )
    (comp (ref "R207")
      (value "1,5kΩ")
      (footprint "eagle-import:CHIP_0805")
      (libsource (lib "eagle-import") (part "R_0805"))
    )
    (comp (ref "R208")
      (value "1,5kΩ")
      (footprint "eagle-import:CHIP_0805")
      (libsource (lib "eagle-import") (part "R_0805"))
    )
    (comp (ref "R209")
      (value "1,5kΩ")
      (footprint "eagle-import:CHIP_0805")
      (libsource (lib "eagle-import") (part "R_0805"))
    )
    (comp (ref "R210")
      (value "1,5kΩ")
      (footprint "eagle-import:CHIP_0805")
      (libsource (lib "eagle-import") (part "R_0805"))
    )
    (comp (ref "R211")
      (value "1,5kΩ")
      (footprint "eagle-import:CHIP_0805")
      (libsource (lib "eagle-import") (part "R_0805"))
    )
    (comp (ref "R212")
      (value "1,5kΩ")
      (footprint "eagle-import:CHIP_0805")
      (libsource (lib "eagle-import") (part "R_0805"))
    )
    (comp (ref "R213")
      (value "1,5kΩ")
      (footprint "eagle-import:CHIP_0805")
      (libsource (lib "eagle-import") (part "R_0805"))
    )
    (comp (ref "R214")
      (value "1,5kΩ")
      (footprint "eagle-import:CHIP_0805")
      (libsource (lib "eagle-import") (part "R_0805"))
    )
    (comp (ref "R215")
      (value "1,5kΩ")
      (footprint "eagle-import:CHIP_0805")
      (libsource (lib "eagle-import") (part "R_0805"))
    )
    (comp (ref "R216")
      (value "1,5kΩ")
      (footprint "eagle-import:CHIP_0805")
      (libsource (lib "eagle-import") (part "R_0805"))
    )
  )
  (nets
    (net (code "1") (name "+5V") (class "Default")
      (node (ref "5V") (pin "1") (pinfunction "1_1") (pintype "passive"))
      (node (ref "C101") (pin "1") (pinfunction "1_1") (pintype "passive"))
      (node (ref "C104") (pin "1") (pinfunction "1_1") (pintype "passive"))
      (node (ref "C105") (pin "1") (pinfunction "1_1") (pintype "passive"))
      (node (ref "C110") (pin "1") (pinfunction "1_1") (pintype "passive"))
      (node (ref "C111") (pin "1") (pinfunction "1_1") (pintype "passive"))
      (node (ref "C112") (pin "1") (pinfunction "1_1") (pintype "passive"))
      (node (ref "C403") (pin "1") (pinfunction "1_1") (pintype "passive"))
      (node (ref "C404") (pin "1") (pinfunction "1_1") (pintype "passive"))
      (node (ref "D402") (pin "A") (pinfunction "A_A") (pintype "passive"))
      (node (ref "IC101") (pin "21") (pinfunction "VCC_21") (pintype "power_in"))
      (node (ref "IC101") (pin "3") (pinfunction "UVCC_3") (pintype "power_in"))
      (node (ref "IC101") (pin "52") (pinfunction "VCC_52") (pintype "power_in"))
      (node (ref "IC101") (pin "64") (pinfunction "AVCC_64") (pintype "power_in"))
      (node (ref "IC102") (pin "8") (pinfunction "VCC_8") (pintype "power_in"))
      (node (ref "IC103") (pin "16") (pinfunction "VCC_16") (pintype "power_in"))
      (node (ref "IC402") (pin "8") (pinfunction "VCC_8") (pintype "power_in"))
      (node (ref "L401") (pin "1") (pinfunction "1_1") (pintype "passive"))
      (node (ref "Q301") (pin "2") (pinfunction "E_2") (pintype "passive"))
      (node (ref "Q302") (pin "2") (pinfunction "E_2") (pintype "passive"))
      (node (ref "Q303") (pin "2") (pinfunction "E_2") (pintype "passive"))
      (node (ref "Q304") (pin "2") (pinfunction "E_2") (pintype "passive"))
      (node (ref "Q305") (pin "2") (pinfunction "E_2") (pintype "passive"))
      (node (ref "Q306") (pin "2") (pinfunction "E_2") (pintype "passive"))
      (node (ref "Q307") (pin "2") (pinfunction "E_2") (pintype "passive"))
      (node (ref "Q308") (pin "2") (pinfunction "E_2") (pintype "passive"))
      (node (ref "R103") (pin "2") (pinfunction "2_2") (pintype "passive"))
      (node (ref "R104") (pin "2") (pinfunction "2_2") (pintype "passive"))
      (node (ref "R105") (pin "2") (pinfunction "2_2") (pintype "passive"))
      (node (ref "R113") (pin "2") (pinfunction "2_2") (pintype "passive"))
      (node (ref "R401") (pin "2") (pinfunction "2_2") (pintype "passive"))
      (node (ref "S101") (pin "P$1") (pinfunction "P$1_P$1") (pintype "passive"))
      (node (ref "S103") (pin "13") (pinfunction "3_13") (pintype "passive"))
      (node (ref "S103") (pin "23") (pinfunction "3_23") (pintype "passive"))
      (node (ref "S103") (pin "33") (pinfunction "3_33") (pintype "passive"))
      (node (ref "S103") (pin "43") (pinfunction "3_43") (pintype "passive"))
      (node (ref "S103") (pin "53") (pinfunction "3_53") (pintype "passive"))
      (node (ref "S103") (pin "63") (pinfunction "3_63") (pintype "passive"))
      (node (ref "S103") (pin "73") (pinfunction "3_73") (pintype "passive"))
      (node (ref "X102") (pin "VCC") (pinfunction "VCC_VCC") (pintype "passive"))
      (node (ref "X103") (pin "1") (pinfunction "A_1") (pintype "passive"))
      (node (ref "X103") (pin "34") (pinfunction "A_34") (pintype "passive"))
      (node (ref "X303") (pin "1") (pinfunction "A_1") (pintype "passive"))
      (node (ref "X303") (pin "34") (pinfunction "A_34") (pintype "passive"))
    )
    (net (code "2") (name "C1") (class "Default")
      (node (ref "IC101") (pin "31") (pinfunction "(T1)PD6_31") (pintype "bidirectional"))
      (node (ref "IC103") (pin "7") (pinfunction "CK_7") (pintype "input"))
    )
    (net (code "3") (name "C2") (class "Default")
      (node (ref "IC101") (pin "32") (pinfunction "(T0)PD7_32") (pintype "bidirectional"))
      (node (ref "IC103") (pin "15") (pinfunction "SH/~{LD}_15") (pintype "input"))
    )
    (net (code "4") (name "DI") (class "Default")
      (node (ref "IC101") (pin "34") (pinfunction "(RD)PE1_34") (pintype "bidirectional"))
      (node (ref "IC103") (pin "13") (pinfunction "QH_13") (pintype "output"))
    )
    (net (code "5") (name "GND") (class "Default")
      (node (ref "0V") (pin "1") (pinfunction "1_1") (pintype "passive"))
      (node (ref "C101") (pin "2") (pinfunction "2_2") (pintype "passive"))
      (node (ref "C102") (pin "2") (pinfunction "2_2") (pintype "passive"))
      (node (ref "C103") (pin "2") (pinfunction "2_2") (pintype "passive"))
      (node (ref "C104") (pin "2") (pinfunction "2_2") (pintype "passive"))
      (node (ref "C105") (pin "2") (pinfunction "2_2") (pintype "passive"))
      (node (ref "C106") (pin "2") (pinfunction "2_2") (pintype "passive"))
      (node (ref "C107") (pin "2") (pinfunction "2_2") (pintype "passive"))
      (node (ref "C108") (pin "2") (pinfunction "2_2") (pintype "passive"))
      (node (ref "C109") (pin "2") (pinfunction "2_2") (pintype "passive"))
      (node (ref "C110") (pin "2") (pinfunction "2_2") (pintype "passive"))
      (node (ref "C111") (pin "2") (pinfunction "2_2") (pintype "passive"))
      (node (ref "C112") (pin "2") (pinfunction "2_2") (pintype "passive"))
      (node (ref "C401") (pin "2") (pinfunction "2_2") (pintype "passive"))
      (node (ref "C402") (pin "2") (pinfunction "2_2") (pintype "passive"))
      (node (ref "C403") (pin "2") (pinfunction "2_2") (pintype "passive"))
      (node (ref "C404") (pin "2") (pinfunction "2_2") (pintype "passive"))
      (node (ref "D101") (pin "A") (pinfunction "A_A") (pintype "passive"))
      (node (ref "D102") (pin "2") (pinfunction "C_2") (pintype "passive"))
      (node (ref "D103") (pin "2") (pinfunction "C_2") (pintype "passive"))
      (node (ref "D104") (pin "2") (pinfunction "C_2") (pintype "passive"))
      (node (ref "D105") (pin "2") (pinfunction "C_2") (pintype "passive"))
      (node (ref "G101") (pin "-") (pinfunction "-_-") (pintype "passive"))
      (node (ref "GND") (pin "1") (pinfunction "1_1") (pintype "passive"))
      (node (ref "IC101") (pin "22") (pinfunction "GND_22") (pintype "power_in"))
      (node (ref "IC101") (pin "53") (pinfunction "GND_53") (pintype "power_in"))
      (node (ref "IC101") (pin "6") (pinfunction "UGND_6") (pintype "power_in"))
      (node (ref "IC101") (pin "63") (pinfunction "GND_63") (pintype "power_in"))
      (node (ref "IC102") (pin "5") (pinfunction "GND_5") (pintype "power_in"))
      (node (ref "IC103") (pin "1") (pinfunction "SI_1") (pintype "input"))
      (node (ref "IC103") (pin "14") (pinfunction "H_14") (pintype "input"))
      (node (ref "IC103") (pin "6") (pinfunction "CKI_6") (pintype "input"))
      (node (ref "IC103") (pin "8") (pinfunction "GND_8") (pintype "power_in"))
      (node (ref "IC301") (pin "3") (pinfunction "E_3") (pintype "passive"))
      (node (ref "IC302") (pin "3") (pinfunction "E_3") (pintype "passive"))
      (node (ref "IC303") (pin "3") (pinfunction "E_3") (pintype "passive"))
      (node (ref "IC304") (pin "3") (pinfunction "E_3") (pintype "passive"))
      (node (ref "IC305") (pin "3") (pinfunction "E_3") (pintype "passive"))
      (node (ref "IC306") (pin "3") (pinfunction "E_3") (pintype "passive"))
      (node (ref "IC307") (pin "3") (pinfunction "E_3") (pintype "passive"))
      (node (ref "IC308") (pin "3") (pinfunction "E_3") (pintype "passive"))
      (node (ref "IC401") (pin "4") (pinfunction "GND_4") (pintype "power_in"))
      (node (ref "IC402") (pin "1") (pinfunction "E0_1") (pintype "input"))
      (node (ref "IC402") (pin "2") (pinfunction "E1_2") (pintype "input"))
      (node (ref "IC402") (pin "3") (pinfunction "E2_3") (pintype "input"))
      (node (ref "IC402") (pin "4") (pinfunction "GND_4") (pintype "power_in"))
      (node (ref "K401") (pin "4") (pinfunction "K_4") (pintype "passive"))
      (node (ref "K402") (pin "4") (pinfunction "K_4") (pintype "passive"))
      (node (ref "K403") (pin "4") (pinfunction "K_4") (pintype "passive"))
      (node (ref "K404") (pin "4") (pinfunction "K_4") (pintype "passive"))
      (node (ref "K405") (pin "4") (pinfunction "K_4") (pintype "passive"))
      (node (ref "K406") (pin "4") (pinfunction "K_4") (pintype "passive"))
      (node (ref "K407") (pin "4") (pinfunction "K_4") (pintype "passive"))
      (node (ref "K408") (pin "4") (pinfunction "K_4") (pintype "passive"))
      (node (ref "Q101") (pin "2") (pinfunction "G_2") (pintype "passive"))
      (node (ref "Q101") (pin "4") (pinfunction "G_4") (pintype "passive"))
      (node (ref "Q401") (pin "G") (pinfunction "G_G") (pintype "passive"))
      (node (ref "R107") (pin "1A") (pinfunction "1_1A") (pintype "passive"))
      (node (ref "R107") (pin "2A") (pinfunction "3_2A") (pintype "passive"))
      (node (ref "R107") (pin "3A") (pinfunction "5_3A") (pintype "passive"))
      (node (ref "R107") (pin "4A") (pinfunction "7_4A") (pintype "passive"))
      (node (ref "R108") (pin "1A") (pinfunction "1_1A") (pintype "passive"))
      (node (ref "R108") (pin "2A") (pinfunction "3_2A") (pintype "passive"))
      (node (ref "R108") (pin "3A") (pinfunction "5_3A") (pintype "passive"))
      (node (ref "R108") (pin "4A") (pinfunction "7_4A") (pintype "passive"))
      (node (ref "R201") (pin "1") (pinfunction "1_1") (pintype "passive"))
      (node (ref "R202") (pin "1") (pinfunction "1_1") (pintype "passive"))
      (node (ref "R203") (pin "1") (pinfunction "1_1") (pintype "passive"))
      (node (ref "R204") (pin "1") (pinfunction "1_1") (pintype "passive"))
      (node (ref "R205") (pin "1") (pinfunction "1_1") (pintype "passive"))
      (node (ref "R206") (pin "1") (pinfunction "1_1") (pintype "passive"))
      (node (ref "R207") (pin "1") (pinfunction "1_1") (pintype "passive"))
      (node (ref "R208") (pin "1") (pinfunction "1_1") (pintype "passive"))
      (node (ref "R209") (pin "1") (pinfunction "1_1") (pintype "passive"))
      (node (ref "R210") (pin "1") (pinfunction "1_1") (pintype "passive"))
      (node (ref "R211") (pin "1") (pinfunction "1_1") (pintype "passive"))
      (node (ref "R212") (pin "1") (pinfunction "1_1") (pintype "passive"))
      (node (ref "R213") (pin "1") (pinfunction "1_1") (pintype "passive"))
      (node (ref "R214") (pin "1") (pinfunction "1_1") (pintype "passive"))
      (node (ref "R215") (pin "1") (pinfunction "1_1") (pintype "passive"))
      (node (ref "R216") (pin "1") (pinfunction "1_1") (pintype "passive"))
      (node (ref "R402") (pin "2") (pinfunction "2_2") (pintype "passive"))
      (node (ref "S102") (pin "1") (pinfunction "P_1") (pintype "passive"))
      (node (ref "S102") (pin "2") (pinfunction "P_2") (pintype "passive"))
      (node (ref "V401") (pin "3") (pinfunction "-VOUT_3") (pintype "passive"))
      (node (ref "V402") (pin "5") (pinfunction "-VOUT_5") (pintype "passive"))
      (node (ref "X101") (pin "5") (pinfunction "GND_5") (pintype "power_in"))
      (node (ref "X102") (pin "GND") (pinfunction "GND_GND") (pintype "passive"))
      (node (ref "X103") (pin "2") (pinfunction "A_2") (pintype "passive"))
      (node (ref "X103") (pin "33") (pinfunction "A_33") (pintype "passive"))
      (node (ref "X103") (pin "4") (pinfunction "A_4") (pintype "passive"))
      (node (ref "X303") (pin "2") (pinfunction "A_2") (pintype "passive"))
      (node (ref "X303") (pin "33") (pinfunction "A_33") (pintype "passive"))
      (node (ref "X303") (pin "4") (pinfunction "A_4") (pintype "passive"))
    )
    (net (code "6") (name "GNDIO") (class "Default")
      (node (ref "C301") (pin "2") (pinfunction "2_2") (pintype "passive"))
      (node (ref "C302") (pin "2") (pinfunction "2_2") (pintype "passive"))
      (node (ref "C303") (pin "2") (pinfunction "2_2") (pintype "passive"))
      (node (ref "C304") (pin "2") (pinfunction "2_2") (pintype "passive"))
      (node (ref "C305") (pin "2") (pinfunction "2_2") (pintype "passive"))
      (node (ref "C306") (pin "2") (pinfunction "2_2") (pintype "passive"))
      (node (ref "C307") (pin "2") (pinfunction "2_2") (pintype "passive"))
      (node (ref "C308") (pin "2") (pinfunction "2_2") (pintype "passive"))
      (node (ref "D302") (pin "A") (pinfunction "A_A") (pintype "passive"))
      (node (ref "D304") (pin "A") (pinfunction "A_A") (pintype "passive"))
      (node (ref "D306") (pin "A") (pinfunction "A_A") (pintype "passive"))
      (node (ref "D308") (pin "A") (pinfunction "A_A") (pintype "passive"))
      (node (ref "D310") (pin "A") (pinfunction "A_A") (pintype "passive"))
      (node (ref "D312") (pin "A") (pinfunction "A_A") (pintype "passive"))
      (node (ref "D314") (pin "A") (pinfunction "A_A") (pintype "passive"))
      (node (ref "D316") (pin "A") (pinfunction "A_A") (pintype "passive"))
      (node (ref "IC301") (pin "2") (pinfunction "K_2") (pintype "passive"))
      (node (ref "IC302") (pin "2") (pinfunction "K_2") (pintype "passive"))
      (node (ref "IC303") (pin "2") (pinfunction "K_2") (pintype "passive"))
      (node (ref "IC304") (pin "2") (pinfunction "K_2") (pintype "passive"))
      (node (ref "IC305") (pin "2") (pinfunction "K_2") (pintype "passive"))
      (node (ref "IC306") (pin "2") (pinfunction "K_2") (pintype "passive"))
      (node (ref "IC307") (pin "2") (pinfunction "K_2") (pintype "passive"))
      (node (ref "IC308") (pin "2") (pinfunction "K_2") (pintype "passive"))
      (node (ref "N") (pin "1") (pinfunction "1_1") (pintype "passive"))
      (node (ref "X301") (pin "P$1") (pinfunction "A_P$1") (pintype "passive"))
      (node (ref "X301") (pin "P$2") (pinfunction "A_P$2") (pintype "passive"))
      (node (ref "X302") (pin "1") (pinfunction "A_1") (pintype "passive"))
      (node (ref "X302") (pin "2") (pinfunction "A_2") (pintype "passive"))
    )
    (net (code "7") (name "IN0") (class "Default")
      (node (ref "D201") (pin "1") (pinfunction "A_1") (pintype "passive"))
      (node (ref "IC101") (pin "35") (pinfunction "(A8)PC0_35") (pintype "bidirectional"))
      (node (ref "X103") (pin "18") (pinfunction "A_18") (pintype "passive"))
    )
    (net (code "8") (name "IN1") (class "Default")
      (node (ref "D202") (pin "1") (pinfunction "A_1") (pintype "passive"))
      (node (ref "IC101") (pin "36") (pinfunction "(A9)PC1_36") (pintype "bidirectional"))
      (node (ref "X103") (pin "20") (pinfunction "A_20") (pintype "passive"))
    )
    (net (code "9") (name "IN2") (class "Default")
      (node (ref "D203") (pin "1") (pinfunction "A_1") (pintype "passive"))
      (node (ref "IC101") (pin "37") (pinfunction "(A10)PC2_37") (pintype "bidirectional"))
      (node (ref "X103") (pin "22") (pinfunction "A_22") (pintype "passive"))
    )
    (net (code "10") (name "IN3") (class "Default")
      (node (ref "D204") (pin "1") (pinfunction "A_1") (pintype "passive"))
      (node (ref "IC101") (pin "38") (pinfunction "(A11/T.3)PC3_38") (pintype "bidirectional"))
      (node (ref "X103") (pin "24") (pinfunction "A_24") (pintype "passive"))
    )
    (net (code "11") (name "IN4") (class "Default")
      (node (ref "D205") (pin "1") (pinfunction "A_1") (pintype "passive"))
      (node (ref "IC101") (pin "39") (pinfunction "(A12/OC.3C)PC4_39") (pintype "bidirectional"))
      (node (ref "X103") (pin "26") (pinfunction "A_26") (pintype "passive"))
    )
    (net (code "12") (name "IN5") (class "Default")
      (node (ref "D206") (pin "1") (pinfunction "A_1") (pintype "passive"))
      (node (ref "IC101") (pin "40") (pinfunction "(A13/OC.3B)PC5_40") (pintype "bidirectional"))
      (node (ref "X103") (pin "28") (pinfunction "A_28") (pintype "passive"))
    )
    (net (code "13") (name "IN6") (class "Default")
      (node (ref "D207") (pin "1") (pinfunction "A_1") (pintype "passive"))
      (node (ref "IC101") (pin "41") (pinfunction "(A14/OC.3A)PC6_41") (pintype "bidirectional"))
      (node (ref "X103") (pin "30") (pinfunction "A_30") (pintype "passive"))
    )
    (net (code "14") (name "IN7") (class "Default")
      (node (ref "D208") (pin "1") (pinfunction "A_1") (pintype "passive"))
      (node (ref "IC101") (pin "42") (pinfunction "(A15/IC.3/CLKO)PC7_42") (pintype "bidirectional"))
      (node (ref "X103") (pin "32") (pinfunction "A_32") (pintype "passive"))
    )
    (net (code "15") (name "LED1") (class "Default")
      (node (ref "IC101") (pin "15") (pinfunction "(PCINT5/OC.1A)PB5_15") (pintype "bidirectional"))
      (node (ref "R109") (pin "2") (pinfunction "2_2") (pintype "passive"))
    )
    (net (code "16") (name "LED2") (class "Default")
      (node (ref "IC101") (pin "16") (pinfunction "(PCINT6/OC.1B)PB6_16") (pintype "bidirectional"))
      (node (ref "R110") (pin "2") (pinfunction "2_2") (pintype "passive"))
    )
    (net (code "17") (name "LED3") (class "Default")
      (node (ref "IC101") (pin "17") (pinfunction "(PCINT7/OC.0A/OC.1C)PB7_17") (pintype "bidirectional"))
      (node (ref "R111") (pin "2") (pinfunction "2_2") (pintype "passive"))
    )
    (net (code "18") (name "MISO") (class "Default")
      (node (ref "IC101") (pin "13") (pinfunction "(PDO/PCINT3/MISO)PB3_13") (pintype "bidirectional"))
      (node (ref "X102") (pin "MISO") (pinfunction "MISO_MISO") (pintype "passive"))
    )
    (net (code "19") (name "MOSI") (class "Default")
      (node (ref "IC101") (pin "12") (pinfunction "(PDI/PCINT2/MOSI)PB2_12") (pintype "bidirectional"))
      (node (ref "X102") (pin "MOSI") (pinfunction "MOSI_MOSI") (pintype "passive"))
    )
    (net (code "20") (name "Net-(C102-Pad1)") (class "Default")
      (node (ref "C102") (pin "1") (pinfunction "1_1") (pintype "passive"))
      (node (ref "X101") (pin "S1") (pinfunction "SHIELD_S1") (pintype "passive"))
      (node (ref "X101") (pin "S2") (pinfunction "SHIELD_S2") (pintype "passive"))
    )
    (net (code "21") (name "Net-(C301-Pad1)") (class "Default")
      (node (ref "C301") (pin "1") (pinfunction "1_1") (pintype "passive"))
      (node (ref "D301") (pin "K") (pinfunction "K_K") (pintype "passive"))
      (node (ref "D302") (pin "K") (pinfunction "K_K") (pintype "passive"))
      (node (ref "R305") (pin "2") (pinfunction "2_2") (pintype "passive"))
    )
    (net (code "22") (name "Net-(C302-Pad1)") (class "Default")
      (node (ref "C302") (pin "1") (pinfunction "1_1") (pintype "passive"))
      (node (ref "D303") (pin "K") (pinfunction "K_K") (pintype "passive"))
      (node (ref "D304") (pin "K") (pinfunction "K_K") (pintype "passive"))
      (node (ref "R306") (pin "2") (pinfunction "2_2") (pintype "passive"))
    )
    (net (code "23") (name "Net-(C303-Pad1)") (class "Default")
      (node (ref "C303") (pin "1") (pinfunction "1_1") (pintype "passive"))
      (node (ref "D305") (pin "K") (pinfunction "K_K") (pintype "passive"))
      (node (ref "D306") (pin "K") (pinfunction "K_K") (pintype "passive"))
      (node (ref "R311") (pin "2") (pinfunction "2_2") (pintype "passive"))
    )
    (net (code "24") (name "Net-(C304-Pad1)") (class "Default")
      (node (ref "C304") (pin "1") (pinfunction "1_1") (pintype "passive"))
      (node (ref "D307") (pin "K") (pinfunction "K_K") (pintype "passive"))
      (node (ref "D308") (pin "K") (pinfunction "K_K") (pintype "passive"))
      (node (ref "R312") (pin "2") (pinfunction "2_2") (pintype "passive"))
    )
    (net (code "25") (name "Net-(C305-Pad1)") (class "Default")
      (node (ref "C305") (pin "1") (pinfunction "1_1") (pintype "passive"))
      (node (ref "D309") (pin "K") (pinfunction "K_K") (pintype "passive"))
      (node (ref "D310") (pin "K") (pinfunction "K_K") (pintype "passive"))
      (node (ref "R317") (pin "2") (pinfunction "2_2") (pintype "passive"))
    )
    (net (code "26") (name "Net-(C306-Pad1)") (class "Default")
      (node (ref "C306") (pin "1") (pinfunction "1_1") (pintype "passive"))
      (node (ref "D311") (pin "K") (pinfunction "K_K") (pintype "passive"))
      (node (ref "D312") (pin "K") (pinfunction "K_K") (pintype "passive"))
      (node (ref "R318") (pin "2") (pinfunction "2_2") (pintype "passive"))
    )
    (net (code "27") (name "Net-(C307-Pad1)") (class "Default")
      (node (ref "C307") (pin "1") (pinfunction "1_1") (pintype "passive"))
      (node (ref "D313") (pin "K") (pinfunction "K_K") (pintype "passive"))
      (node (ref "D314") (pin "K") (pinfunction "K_K") (pintype "passive"))
      (node (ref "R323") (pin "2") (pinfunction "2_2") (pintype "passive"))
    )
    (net (code "28") (name "Net-(C308-Pad1)") (class "Default")
      (node (ref "C308") (pin "1") (pinfunction "1_1") (pintype "passive"))
      (node (ref "D315") (pin "K") (pinfunction "K_K") (pintype "passive"))
      (node (ref "D316") (pin "K") (pinfunction "K_K") (pintype "passive"))
      (node (ref "R324") (pin "2") (pinfunction "2_2") (pintype "passive"))
    )
    (net (code "29") (name "Net-(D102-A)") (class "Default")
      (node (ref "D102") (pin "1") (pinfunction "A_1") (pintype "passive"))
      (node (ref "R109") (pin "1") (pinfunction "1_1") (pintype "passive"))
    )
    (net (code "30") (name "Net-(D103-A)") (class "Default")
      (node (ref "D103") (pin "1") (pinfunction "A_1") (pintype "passive"))
      (node (ref "R110") (pin "1") (pinfunction "1_1") (pintype "passive"))
    )
    (net (code "31") (name "Net-(D104-A)") (class "Default")
      (node (ref "D104") (pin "1") (pinfunction "A_1") (pintype "passive"))
      (node (ref "R111") (pin "1") (pinfunction "1_1") (pintype "passive"))
    )
    (net (code "32") (name "Net-(D105-A)") (class "Default")
      (node (ref "D105") (pin "1") (pinfunction "A_1") (pintype "passive"))
      (node (ref "R113") (pin "1") (pinfunction "1_1") (pintype "passive"))
    )
    (net (code "33") (name "Net-(D201-C)") (class "Default")
      (node (ref "D201") (pin "2") (pinfunction "C_2") (pintype "passive"))
      (node (ref "R201") (pin "2") (pinfunction "2_2") (pintype "passive"))
    )
    (net (code "34") (name "Net-(D202-C)") (class "Default")
      (node (ref "D202") (pin "2") (pinfunction "C_2") (pintype "passive"))
      (node (ref "R202") (pin "2") (pinfunction "2_2") (pintype "passive"))
    )
    (net (code "35") (name "Net-(D203-C)") (class "Default")
      (node (ref "D203") (pin "2") (pinfunction "C_2") (pintype "passive"))
      (node (ref "R203") (pin "2") (pinfunction "2_2") (pintype "passive"))
    )
    (net (code "36") (name "Net-(D204-C)") (class "Default")
      (node (ref "D204") (pin "2") (pinfunction "C_2") (pintype "passive"))
      (node (ref "R204") (pin "2") (pinfunction "2_2") (pintype "passive"))
    )
    (net (code "37") (name "Net-(D205-C)") (class "Default")
      (node (ref "D205") (pin "2") (pinfunction "C_2") (pintype "passive"))
      (node (ref "R205") (pin "2") (pinfunction "2_2") (pintype "passive"))
    )
    (net (code "38") (name "Net-(D206-C)") (class "Default")
      (node (ref "D206") (pin "2") (pinfunction "C_2") (pintype "passive"))
      (node (ref "R206") (pin "2") (pinfunction "2_2") (pintype "passive"))
    )
    (net (code "39") (name "Net-(D207-C)") (class "Default")
      (node (ref "D207") (pin "2") (pinfunction "C_2") (pintype "passive"))
      (node (ref "R207") (pin "2") (pinfunction "2_2") (pintype "passive"))
    )
    (net (code "40") (name "Net-(D208-C)") (class "Default")
      (node (ref "D208") (pin "2") (pinfunction "C_2") (pintype "passive"))
      (node (ref "R208") (pin "2") (pinfunction "2_2") (pintype "passive"))
    )
    (net (code "41") (name "Net-(D209-C)") (class "Default")
      (node (ref "D209") (pin "2") (pinfunction "C_2") (pintype "passive"))
      (node (ref "R209") (pin "2") (pinfunction "2_2") (pintype "passive"))
    )
    (net (code "42") (name "Net-(D210-C)") (class "Default")
      (node (ref "D210") (pin "2") (pinfunction "C_2") (pintype "passive"))
      (node (ref "R210") (pin "2") (pinfunction "2_2") (pintype "passive"))
    )
    (net (code "43") (name "Net-(D211-C)") (class "Default")
      (node (ref "D211") (pin "2") (pinfunction "C_2") (pintype "passive"))
      (node (ref "R211") (pin "2") (pinfunction "2_2") (pintype "passive"))
    )
    (net (code "44") (name "Net-(D212-C)") (class "Default")
      (node (ref "D212") (pin "2") (pinfunction "C_2") (pintype "passive"))
      (node (ref "R212") (pin "2") (pinfunction "2_2") (pintype "passive"))
    )
    (net (code "45") (name "Net-(D213-C)") (class "Default")
      (node (ref "D213") (pin "2") (pinfunction "C_2") (pintype "passive"))
      (node (ref "R213") (pin "2") (pinfunction "2_2") (pintype "passive"))
    )
    (net (code "46") (name "Net-(D214-C)") (class "Default")
      (node (ref "D214") (pin "2") (pinfunction "C_2") (pintype "passive"))
      (node (ref "R214") (pin "2") (pinfunction "2_2") (pintype "passive"))
    )
    (net (code "47") (name "Net-(D215-C)") (class "Default")
      (node (ref "D215") (pin "2") (pinfunction "C_2") (pintype "passive"))
      (node (ref "R215") (pin "2") (pinfunction "2_2") (pintype "passive"))
    )
    (net (code "48") (name "Net-(D216-C)") (class "Default")
      (node (ref "D216") (pin "2") (pinfunction "C_2") (pintype "passive"))
      (node (ref "R216") (pin "2") (pinfunction "2_2") (pintype "passive"))
    )
    (net (code "49") (name "Net-(D301-PadA)") (class "Default")
      (node (ref "D301") (pin "A") (pinfunction "A_A") (pintype "passive"))
      (node (ref "R302") (pin "1") (pinfunction "1_1") (pintype "passive"))
    )
    (net (code "50") (name "Net-(D303-PadA)") (class "Default")
      (node (ref "D303") (pin "A") (pinfunction "A_A") (pintype "passive"))
      (node (ref "R304") (pin "1") (pinfunction "1_1") (pintype "passive"))
    )
    (net (code "51") (name "Net-(D305-PadA)") (class "Default")
      (node (ref "D305") (pin "A") (pinfunction "A_A") (pintype "passive"))
      (node (ref "R308") (pin "1") (pinfunction "1_1") (pintype "passive"))
    )
    (net (code "52") (name "Net-(D307-PadA)") (class "Default")
      (node (ref "D307") (pin "A") (pinfunction "A_A") (pintype "passive"))
      (node (ref "R310") (pin "1") (pinfunction "1_1") (pintype "passive"))
    )
    (net (code "53") (name "Net-(D309-PadA)") (class "Default")
      (node (ref "D309") (pin "A") (pinfunction "A_A") (pintype "passive"))
      (node (ref "R314") (pin "1") (pinfunction "1_1") (pintype "passive"))
    )
    (net (code "54") (name "Net-(D311-PadA)") (class "Default")
      (node (ref "D311") (pin "A") (pinfunction "A_A") (pintype "passive"))
      (node (ref "R316") (pin "1") (pinfunction "1_1") (pintype "passive"))
    )
    (net (code "55") (name "Net-(D313-PadA)") (class "Default")
      (node (ref "D313") (pin "A") (pinfunction "A_A") (pintype "passive"))
      (node (ref "R320") (pin "1") (pinfunction "1_1") (pintype "passive"))
    )
    (net (code "56") (name "Net-(D315-PadA)") (class "Default")
      (node (ref "D315") (pin "A") (pinfunction "A_A") (pintype "passive"))
      (node (ref "R322") (pin "1") (pinfunction "1_1") (pintype "passive"))
    )
    (net (code "57") (name "Net-(F401-Pad1)") (class "Default")
      (node (ref "F401") (pin "1") (pinfunction "1_1") (pintype "passive"))
      (node (ref "L401") (pin "2") (pinfunction "2_2") (pintype "passive"))
    )
    (net (code "58") (name "Net-(IC101-(ADC0)PF0)") (class "Default")
      (node (ref "IC101") (pin "61") (pinfunction "(ADC0)PF0_61") (pintype "bidirectional"))
      (node (ref "X103") (pin "9") (pinfunction "A_9") (pintype "passive"))
    )
    (net (code "59") (name "Net-(IC101-(ADC1)PF1)") (class "Default")
      (node (ref "IC101") (pin "60") (pinfunction "(ADC1)PF1_60") (pintype "bidirectional"))
      (node (ref "X103") (pin "10") (pinfunction "A_10") (pintype "passive"))
    )
    (net (code "60") (name "Net-(IC101-(ADC2)PF2)") (class "Default")
      (node (ref "IC101") (pin "59") (pinfunction "(ADC2)PF2_59") (pintype "bidirectional"))
      (node (ref "X103") (pin "11") (pinfunction "A_11") (pintype "passive"))
    )
    (net (code "61") (name "Net-(IC101-(ADC3)PF3)") (class "Default")
      (node (ref "IC101") (pin "58") (pinfunction "(ADC3)PF3_58") (pintype "bidirectional"))
      (node (ref "X103") (pin "12") (pinfunction "A_12") (pintype "passive"))
    )
    (net (code "62") (name "Net-(IC101-(ALE{slash}HWB)PE2)") (class "Default")
      (node (ref "IC101") (pin "18") (pinfunction "(INT4/TOSC1)PE4_18") (pintype "bidirectional"))
      (node (ref "IC101") (pin "43") (pinfunction "(ALE/HWB)PE2_43") (pintype "bidirectional"))
      (node (ref "R104") (pin "1") (pinfunction "1_1") (pintype "passive"))
      (node (ref "S102") (pin "3") (pinfunction "S_3") (pintype "passive"))
      (node (ref "S102") (pin "4") (pinfunction "S_4") (pintype "passive"))
    )
    (net (code "63") (name "Net-(IC101-(INT.6{slash}AIN.0)PE6)") (class "Default")
      (node (ref "IC101") (pin "1") (pinfunction "(INT.6/AIN.0)PE6_1") (pintype "bidirectional"))
      (node (ref "R106") (pin "2") (pinfunction "2_2") (pintype "passive"))
    )
    (net (code "64") (name "Net-(IC101-(INT.7{slash}AIN.1{slash}UVCON)PE7)") (class "Default")
      (node (ref "D101") (pin "K") (pinfunction "K_K") (pintype "passive"))
      (node (ref "IC101") (pin "2") (pinfunction "(INT.7/AIN.1/UVCON)PE7_2") (pintype "bidirectional"))
      (node (ref "R105") (pin "1") (pinfunction "1_1") (pintype "passive"))
    )
    (net (code "65") (name "Net-(IC101-(IUID)PE3)") (class "Default")
      (node (ref "IC101") (pin "9") (pinfunction "(IUID)PE3_9") (pintype "bidirectional"))
      (node (ref "X101") (pin "4") (pinfunction "ID_4") (pintype "bidirectional"))
    )
    (net (code "66") (name "Net-(IC101-(OC0B{slash}SCL{slash}INT0)PD0)") (class "Default")
      (node (ref "IC101") (pin "25") (pinfunction "(OC0B/SCL/INT0)PD0_25") (pintype "bidirectional"))
      (node (ref "X103") (pin "7") (pinfunction "A_7") (pintype "passive"))
    )
    (net (code "67") (name "Net-(IC101-(OC2B{slash}SDA{slash}INT1)PD1)") (class "Default")
      (node (ref "IC101") (pin "26") (pinfunction "(OC2B/SDA/INT1)PD1_26") (pintype "bidirectional"))
      (node (ref "X103") (pin "8") (pinfunction "A_8") (pintype "passive"))
    )
    (net (code "68") (name "Net-(IC101-(TCK{slash}ADC4)PF4)") (class "Default")
      (node (ref "IC101") (pin "57") (pinfunction "(TCK/ADC4)PF4_57") (pintype "bidirectional"))
      (node (ref "X103") (pin "13") (pinfunction "A_13") (pintype "passive"))
    )
    (net (code "69") (name "Net-(IC101-(TDI{slash}ADC7)PF7)") (class "Default")
      (node (ref "IC101") (pin "54") (pinfunction "(TDI/ADC7)PF7_54") (pintype "bidirectional"))
      (node (ref "X103") (pin "16") (pinfunction "A_16") (pintype "passive"))
    )
    (net (code "70") (name "Net-(IC101-(TDO{slash}ADC6)PF6)") (class "Default")
      (node (ref "IC101") (pin "55") (pinfunction "(TDO/ADC6)PF6_55") (pintype "bidirectional"))
      (node (ref "X103") (pin "15") (pinfunction "A_15") (pintype "passive"))
    )
    (net (code "71") (name "Net-(IC101-(TMS{slash}ADC5)PF5)") (class "Default")
      (node (ref "IC101") (pin "56") (pinfunction "(TMS/ADC5)PF5_56") (pintype "bidirectional"))
      (node (ref "X103") (pin "14") (pinfunction "A_14") (pintype "passive"))
    )
    (net (code "72") (name "Net-(IC101-AREF)") (class "Default")
      (node (ref "C107") (pin "1") (pinfunction "1_1") (pintype "passive"))
      (node (ref "IC101") (pin "62") (pinfunction "AREF_62") (pintype "passive"))
    )
    (net (code "73") (name "Net-(IC101-D+)") (class "Default")
      (node (ref "IC101") (pin "5") (pinfunction "D+_5") (pintype "bidirectional"))
      (node (ref "R102") (pin "2") (pinfunction "2_2") (pintype "passive"))
    )
    (net (code "74") (name "Net-(IC101-D-)") (class "Default")
      (node (ref "IC101") (pin "4") (pinfunction "D-_4") (pintype "bidirectional"))
      (node (ref "R101") (pin "2") (pinfunction "2_2") (pintype "passive"))
    )
    (net (code "75") (name "Net-(IC101-UCAP)") (class "Default")
      (node (ref "C109") (pin "1") (pinfunction "1_1") (pintype "passive"))
      (node (ref "IC101") (pin "7") (pinfunction "UCAP_7") (pintype "passive"))
    )
    (net (code "76") (name "Net-(IC101-VBUS)") (class "Default")
      (node (ref "C106") (pin "1") (pinfunction "1_1") (pintype "passive"))
      (node (ref "IC101") (pin "8") (pinfunction "VBUS_8") (pintype "power_in"))
      (node (ref "S101") (pin "P$2") (pinfunction "P$2_P$2") (pintype "passive"))
      (node (ref "X101") (pin "1") (pinfunction "VBUS_1") (pintype "power_in"))
    )
    (net (code "77") (name "Net-(IC101-XTAL1)") (class "Default")
      (node (ref "C103") (pin "1") (pinfunction "1_1") (pintype "passive"))
      (node (ref "IC101") (pin "24") (pinfunction "XTAL1_24") (pintype "bidirectional"))
      (node (ref "Q101") (pin "1") (pinfunction "1_1") (pintype "passive"))
    )
    (net (code "78") (name "Net-(IC101-XTAL2)") (class "Default")
      (node (ref "C108") (pin "1") (pinfunction "1_1") (pintype "passive"))
      (node (ref "IC101") (pin "23") (pinfunction "XTAL2_23") (pintype "bidirectional"))
      (node (ref "Q101") (pin "3") (pinfunction "2_3") (pintype "passive"))
    )
    (net (code "79") (name "Net-(IC102A-A)") (class "Default")
      (node (ref "IC102") (pin "6") (pinfunction "A_6") (pintype "passive"))
      (node (ref "S103") (pin "84") (pinfunction "4_84") (pintype "passive"))
      (node (ref "X103") (pin "5") (pinfunction "A_5") (pintype "passive"))
    )
    (net (code "80") (name "Net-(IC102A-B)") (class "Default")
      (node (ref "IC102") (pin "7") (pinfunction "B_7") (pintype "passive"))
      (node (ref "R112") (pin "1") (pinfunction "1_1") (pintype "passive"))
      (node (ref "X103") (pin "6") (pinfunction "A_6") (pintype "passive"))
    )
    (net (code "81") (name "Net-(IC103A-A)") (class "Default")
      (node (ref "IC103") (pin "2") (pinfunction "A_2") (pintype "input"))
      (node (ref "R107") (pin "1B") (pinfunction "2_1B") (pintype "passive"))
      (node (ref "S103") (pin "14") (pinfunction "4_14") (pintype "passive"))
    )
    (net (code "82") (name "Net-(IC103A-B)") (class "Default")
      (node (ref "IC103") (pin "3") (pinfunction "B_3") (pintype "input"))
      (node (ref "R107") (pin "2B") (pinfunction "4_2B") (pintype "passive"))
      (node (ref "S103") (pin "24") (pinfunction "4_24") (pintype "passive"))
    )
    (net (code "83") (name "Net-(IC103A-C)") (class "Default")
      (node (ref "IC103") (pin "4") (pinfunction "C_4") (pintype "input"))
      (node (ref "R107") (pin "3B") (pinfunction "6_3B") (pintype "passive"))
      (node (ref "S103") (pin "34") (pinfunction "4_34") (pintype "passive"))
    )
    (net (code "84") (name "Net-(IC103A-D)") (class "Default")
      (node (ref "IC103") (pin "5") (pinfunction "D_5") (pintype "input"))
      (node (ref "R107") (pin "4B") (pinfunction "8_4B") (pintype "passive"))
      (node (ref "S103") (pin "44") (pinfunction "4_44") (pintype "passive"))
    )
    (net (code "85") (name "Net-(IC103A-E)") (class "Default")
      (node (ref "IC103") (pin "10") (pinfunction "E_10") (pintype "input"))
      (node (ref "R108") (pin "1B") (pinfunction "2_1B") (pintype "passive"))
      (node (ref "S103") (pin "54") (pinfunction "4_54") (pintype "passive"))
    )
    (net (code "86") (name "Net-(IC103A-F)") (class "Default")
      (node (ref "IC103") (pin "11") (pinfunction "F_11") (pintype "input"))
      (node (ref "R108") (pin "2B") (pinfunction "4_2B") (pintype "passive"))
      (node (ref "S103") (pin "64") (pinfunction "4_64") (pintype "passive"))
    )
    (net (code "87") (name "Net-(IC103A-G)") (class "Default")
      (node (ref "IC103") (pin "12") (pinfunction "G_12") (pintype "input"))
      (node (ref "R108") (pin "3B") (pinfunction "6_3B") (pintype "passive"))
      (node (ref "S103") (pin "74") (pinfunction "4_74") (pintype "passive"))
    )
    (net (code "88") (name "Net-(IC301-A)") (class "Default")
      (node (ref "IC301") (pin "1") (pinfunction "A_1") (pintype "passive"))
      (node (ref "R305") (pin "1") (pinfunction "1_1") (pintype "passive"))
    )
    (net (code "89") (name "Net-(IC301-C)") (class "Default")
      (node (ref "IC301") (pin "4") (pinfunction "C_4") (pintype "passive"))
      (node (ref "Q301") (pin "1") (pinfunction "B_1") (pintype "passive"))
    )
    (net (code "90") (name "Net-(IC302-A)") (class "Default")
      (node (ref "IC302") (pin "1") (pinfunction "A_1") (pintype "passive"))
      (node (ref "R306") (pin "1") (pinfunction "1_1") (pintype "passive"))
    )
    (net (code "91") (name "Net-(IC302-C)") (class "Default")
      (node (ref "IC302") (pin "4") (pinfunction "C_4") (pintype "passive"))
      (node (ref "Q302") (pin "1") (pinfunction "B_1") (pintype "passive"))
    )
    (net (code "92") (name "Net-(IC303-A)") (class "Default")
      (node (ref "IC303") (pin "1") (pinfunction "A_1") (pintype "passive"))
      (node (ref "R311") (pin "1") (pinfunction "1_1") (pintype "passive"))
    )
    (net (code "93") (name "Net-(IC303-C)") (class "Default")
      (node (ref "IC303") (pin "4") (pinfunction "C_4") (pintype "passive"))
      (node (ref "Q303") (pin "1") (pinfunction "B_1") (pintype "passive"))
    )
    (net (code "94") (name "Net-(IC304-A)") (class "Default")
      (node (ref "IC304") (pin "1") (pinfunction "A_1") (pintype "passive"))
      (node (ref "R312") (pin "1") (pinfunction "1_1") (pintype "passive"))
    )
    (net (code "95") (name "Net-(IC304-C)") (class "Default")
      (node (ref "IC304") (pin "4") (pinfunction "C_4") (pintype "passive"))
      (node (ref "Q304") (pin "1") (pinfunction "B_1") (pintype "passive"))
    )
    (net (code "96") (name "Net-(IC305-A)") (class "Default")
      (node (ref "IC305") (pin "1") (pinfunction "A_1") (pintype "passive"))
      (node (ref "R317") (pin "1") (pinfunction "1_1") (pintype "passive"))
    )
    (net (code "97") (name "Net-(IC305-C)") (class "Default")
      (node (ref "IC305") (pin "4") (pinfunction "C_4") (pintype "passive"))
      (node (ref "Q305") (pin "1") (pinfunction "B_1") (pintype "passive"))
    )
    (net (code "98") (name "Net-(IC306-A)") (class "Default")
      (node (ref "IC306") (pin "1") (pinfunction "A_1") (pintype "passive"))
      (node (ref "R318") (pin "1") (pinfunction "1_1") (pintype "passive"))
    )
    (net (code "99") (name "Net-(IC306-C)") (class "Default")
      (node (ref "IC306") (pin "4") (pinfunction "C_4") (pintype "passive"))
      (node (ref "Q306") (pin "1") (pinfunction "B_1") (pintype "passive"))
    )
    (net (code "100") (name "Net-(IC307-A)") (class "Default")
      (node (ref "IC307") (pin "1") (pinfunction "A_1") (pintype "passive"))
      (node (ref "R323") (pin "1") (pinfunction "1_1") (pintype "passive"))
    )
    (net (code "101") (name "Net-(IC307-C)") (class "Default")
      (node (ref "IC307") (pin "4") (pinfunction "C_4") (pintype "passive"))
      (node (ref "Q307") (pin "1") (pinfunction "B_1") (pintype "passive"))
    )
    (net (code "102") (name "Net-(IC308-A)") (class "Default")
      (node (ref "IC308") (pin "1") (pinfunction "A_1") (pintype "passive"))
      (node (ref "R324") (pin "1") (pinfunction "1_1") (pintype "passive"))
    )
    (net (code "103") (name "Net-(IC308-C)") (class "Default")
      (node (ref "IC308") (pin "4") (pinfunction "C_4") (pintype "passive"))
      (node (ref "Q308") (pin "1") (pinfunction "B_1") (pintype "passive"))
    )
    (net (code "104") (name "Net-(IC401A-SCL)") (class "Default")
      (node (ref "IC401") (pin "6") (pinfunction "SCL_6") (pintype "bidirectional"))
      (node (ref "IC402") (pin "6") (pinfunction "SCL_6") (pintype "open_collector"))
      (node (ref "X303") (pin "7") (pinfunction "A_7") (pintype "passive"))
    )
    (net (code "105") (name "Net-(IC401A-SDA)") (class "Default")
      (node (ref "IC401") (pin "5") (pinfunction "SDA_5") (pintype "bidirectional"))
      (node (ref "IC402") (pin "5") (pinfunction "SDA_5") (pintype "open_collector"))
      (node (ref "X303") (pin "8") (pinfunction "A_8") (pintype "passive"))
    )
    (net (code "106") (name "Net-(IC401A-X1)") (class "Default")
      (node (ref "IC401") (pin "1") (pinfunction "X1_1") (pintype "bidirectional"))
      (node (ref "Q401") (pin "2") (pinfunction "2_2") (pintype "passive"))
    )
    (net (code "107") (name "Net-(IC401A-X2)") (class "Default")
      (node (ref "IC401") (pin "2") (pinfunction "X2_2") (pintype "bidirectional"))
      (node (ref "Q401") (pin "1") (pinfunction "1_1") (pintype "passive"))
    )
    (net (code "108") (name "Net-(IC401B-VCC)") (class "Default")
      (node (ref "C402") (pin "1") (pinfunction "1_1") (pintype "passive"))
      (node (ref "D402") (pin "K") (pinfunction "K_K") (pintype "passive"))
      (node (ref "D403") (pin "K") (pinfunction "K_K") (pintype "passive"))
      (node (ref "IC401") (pin "8") (pinfunction "VCC_8") (pintype "power_in"))
    )
    (net (code "109") (name "Net-(K401-A)") (class "Default")
      (node (ref "K401") (pin "3") (pinfunction "A_3") (pintype "passive"))
      (node (ref "R403") (pin "2") (pinfunction "2_2") (pintype "passive"))
    )
    (net (code "110") (name "Net-(K401-DS1)") (class "Default")
      (node (ref "K401") (pin "1") (pinfunction "DS1_1") (pintype "passive"))
      (node (ref "X406") (pin "P$1") (pinfunction "A_P$1") (pintype "passive"))
      (node (ref "X407") (pin "1") (pinfunction "A_1") (pintype "passive"))
    )
    (net (code "111") (name "Net-(K401-DS2)") (class "Default")
      (node (ref "K401") (pin "2") (pinfunction "DS2_2") (pintype "passive"))
      (node (ref "K402") (pin "2") (pinfunction "DS2_2") (pintype "passive"))
      (node (ref "K403") (pin "2") (pinfunction "DS2_2") (pintype "passive"))
      (node (ref "K404") (pin "2") (pinfunction "DS2_2") (pintype "passive"))
      (node (ref "K405") (pin "2") (pinfunction "DS2_2") (pintype "passive"))
      (node (ref "K406") (pin "2") (pinfunction "DS2_2") (pintype "passive"))
      (node (ref "K407") (pin "2") (pinfunction "DS2_2") (pintype "passive"))
      (node (ref "K408") (pin "2") (pinfunction "DS2_2") (pintype "passive"))
      (node (ref "X408") (pin "1") (pinfunction "A_1") (pintype "passive"))
      (node (ref "X408") (pin "2") (pinfunction "A_2") (pintype "passive"))
      (node (ref "X409") (pin "P$1") (pinfunction "A_P$1") (pintype "passive"))
      (node (ref "X409") (pin "P$2") (pinfunction "A_P$2") (pintype "passive"))
    )
    (net (code "112") (name "Net-(K402-A)") (class "Default")
      (node (ref "K402") (pin "3") (pinfunction "A_3") (pintype "passive"))
      (node (ref "R404") (pin "2") (pinfunction "2_2") (pintype "passive"))
    )
    (net (code "113") (name "Net-(K402-DS1)") (class "Default")
      (node (ref "K402") (pin "1") (pinfunction "DS1_1") (pintype "passive"))
      (node (ref "X406") (pin "P$2") (pinfunction "A_P$2") (pintype "passive"))
      (node (ref "X407") (pin "2") (pinfunction "A_2") (pintype "passive"))
    )
    (net (code "114") (name "Net-(K403-A)") (class "Default")
      (node (ref "K403") (pin "3") (pinfunction "A_3") (pintype "passive"))
      (node (ref "R405") (pin "2") (pinfunction "2_2") (pintype "passive"))
    )
    (net (code "115") (name "Net-(K403-DS1)") (class "Default")
      (node (ref "K403") (pin "1") (pinfunction "DS1_1") (pintype "passive"))
      (node (ref "X406") (pin "P$3") (pinfunction "A_P$3") (pintype "passive"))
      (node (ref "X410") (pin "1") (pinfunction "A_1") (pintype "passive"))
    )
    (net (code "116") (name "Net-(K404-A)") (class "Default")
      (node (ref "K404") (pin "3") (pinfunction "A_3") (pintype "passive"))
      (node (ref "R406") (pin "2") (pinfunction "2_2") (pintype "passive"))
    )
    (net (code "117") (name "Net-(K404-DS1)") (class "Default")
      (node (ref "K404") (pin "1") (pinfunction "DS1_1") (pintype "passive"))
      (node (ref "X406") (pin "P$4") (pinfunction "A_P$4") (pintype "passive"))
      (node (ref "X410") (pin "2") (pinfunction "A_2") (pintype "passive"))
    )
    (net (code "118") (name "Net-(K405-A)") (class "Default")
      (node (ref "K405") (pin "3") (pinfunction "A_3") (pintype "passive"))
      (node (ref "R407") (pin "2") (pinfunction "2_2") (pintype "passive"))
    )
    (net (code "119") (name "Net-(K405-DS1)") (class "Default")
      (node (ref "K405") (pin "1") (pinfunction "DS1_1") (pintype "passive"))
      (node (ref "X406") (pin "P$5") (pinfunction "A_P$5") (pintype "passive"))
      (node (ref "X411") (pin "1") (pinfunction "A_1") (pintype "passive"))
    )
    (net (code "120") (name "Net-(K406-A)") (class "Default")
      (node (ref "K406") (pin "3") (pinfunction "A_3") (pintype "passive"))
      (node (ref "R408") (pin "2") (pinfunction "2_2") (pintype "passive"))
    )
    (net (code "121") (name "Net-(K406-DS1)") (class "Default")
      (node (ref "K406") (pin "1") (pinfunction "DS1_1") (pintype "passive"))
      (node (ref "X406") (pin "P$6") (pinfunction "A_P$6") (pintype "passive"))
      (node (ref "X411") (pin "2") (pinfunction "A_2") (pintype "passive"))
    )
    (net (code "122") (name "Net-(K407-A)") (class "Default")
      (node (ref "K407") (pin "3") (pinfunction "A_3") (pintype "passive"))
      (node (ref "R409") (pin "2") (pinfunction "2_2") (pintype "passive"))
    )
    (net (code "123") (name "Net-(K407-DS1)") (class "Default")
      (node (ref "K407") (pin "1") (pinfunction "DS1_1") (pintype "passive"))
      (node (ref "X406") (pin "P$7") (pinfunction "A_P$7") (pintype "passive"))
      (node (ref "X412") (pin "1") (pinfunction "A_1") (pintype "passive"))
    )
    (net (code "124") (name "Net-(K408-A)") (class "Default")
      (node (ref "K408") (pin "3") (pinfunction "A_3") (pintype "passive"))
      (node (ref "R410") (pin "2") (pinfunction "2_2") (pintype "passive"))
    )
    (net (code "125") (name "Net-(K408-DS1)") (class "Default")
      (node (ref "K408") (pin "1") (pinfunction "DS1_1") (pintype "passive"))
      (node (ref "X406") (pin "P$8") (pinfunction "A_P$8") (pintype "passive"))
      (node (ref "X412") (pin "2") (pinfunction "A_2") (pintype "passive"))
    )
    (net (code "126") (name "Net-(Q301-C)") (class "Default")
      (node (ref "Q301") (pin "3") (pinfunction "C_3") (pintype "passive"))
      (node (ref "X303") (pin "18") (pinfunction "A_18") (pintype "passive"))
    )
    (net (code "127") (name "Net-(Q302-C)") (class "Default")
      (node (ref "Q302") (pin "3") (pinfunction "C_3") (pintype "passive"))
      (node (ref "X303") (pin "26") (pinfunction "A_26") (pintype "passive"))
    )
    (net (code "128") (name "Net-(Q303-C)") (class "Default")
      (node (ref "Q303") (pin "3") (pinfunction "C_3") (pintype "passive"))
      (node (ref "X303") (pin "20") (pinfunction "A_20") (pintype "passive"))
    )
    (net (code "129") (name "Net-(Q304-C)") (class "Default")
      (node (ref "Q304") (pin "3") (pinfunction "C_3") (pintype "passive"))
      (node (ref "X303") (pin "28") (pinfunction "A_28") (pintype "passive"))
    )
    (net (code "130") (name "Net-(Q305-C)") (class "Default")
      (node (ref "Q305") (pin "3") (pinfunction "C_3") (pintype "passive"))
      (node (ref "X303") (pin "22") (pinfunction "A_22") (pintype "passive"))
    )
    (net (code "131") (name "Net-(Q306-C)") (class "Default")
      (node (ref "Q306") (pin "3") (pinfunction "C_3") (pintype "passive"))
      (node (ref "X303") (pin "30") (pinfunction "A_30") (pintype "passive"))
    )
    (net (code "132") (name "Net-(Q307-C)") (class "Default")
      (node (ref "Q307") (pin "3") (pinfunction "C_3") (pintype "passive"))
      (node (ref "X303") (pin "24") (pinfunction "A_24") (pintype "passive"))
    )
    (net (code "133") (name "Net-(Q308-C)") (class "Default")
      (node (ref "Q308") (pin "3") (pinfunction "C_3") (pintype "passive"))
      (node (ref "X303") (pin "32") (pinfunction "A_32") (pintype "passive"))
    )
    (net (code "134") (name "Net-(R301-Pad1)") (class "Default")
      (node (ref "R301") (pin "1") (pinfunction "1_1") (pintype "passive"))
      (node (ref "R302") (pin "2") (pinfunction "2_2") (pintype "passive"))
    )
    (net (code "135") (name "Net-(R303-Pad1)") (class "Default")
      (node (ref "R303") (pin "1") (pinfunction "1_1") (pintype "passive"))
      (node (ref "R304") (pin "2") (pinfunction "2_2") (pintype "passive"))
    )
    (net (code "136") (name "Net-(R307-Pad1)") (class "Default")
      (node (ref "R307") (pin "1") (pinfunction "1_1") (pintype "passive"))
      (node (ref "R308") (pin "2") (pinfunction "2_2") (pintype "passive"))
    )
    (net (code "137") (name "Net-(R309-Pad1)") (class "Default")
      (node (ref "R309") (pin "1") (pinfunction "1_1") (pintype "passive"))
      (node (ref "R310") (pin "2") (pinfunction "2_2") (pintype "passive"))
    )
    (net (code "138") (name "Net-(R313-Pad1)") (class "Default")
      (node (ref "R313") (pin "1") (pinfunction "1_1") (pintype "passive"))
      (node (ref "R314") (pin "2") (pinfunction "2_2") (pintype "passive"))
    )
    (net (code "139") (name "Net-(R315-Pad1)") (class "Default")
      (node (ref "R315") (pin "1") (pinfunction "1_1") (pintype "passive"))
      (node (ref "R316") (pin "2") (pinfunction "2_2") (pintype "passive"))
    )
    (net (code "140") (name "Net-(R319-Pad1)") (class "Default")
      (node (ref "R319") (pin "1") (pinfunction "1_1") (pintype "passive"))
      (node (ref "R320") (pin "2") (pinfunction "2_2") (pintype "passive"))
    )
    (net (code "141") (name "Net-(R321-Pad1)") (class "Default")
      (node (ref "R321") (pin "1") (pinfunction "1_1") (pintype "passive"))
      (node (ref "R322") (pin "2") (pinfunction "2_2") (pintype "passive"))
    )
    (net (code "142") (name "Net-(S103H-3)") (class "Default")
      (node (ref "R112") (pin "2") (pinfunction "2_2") (pintype "passive"))
      (node (ref "S103") (pin "83") (pinfunction "3_83") (pintype "passive"))
    )
    (net (code "143") (name "Net-(V401-+VIN)") (class "Default")
      (node (ref "D401") (pin "K") (pinfunction "K_K") (pintype "passive"))
      (node (ref "V401") (pin "2") (pinfunction "+VIN_2") (pintype "passive"))
      (node (ref "V402") (pin "1") (pinfunction "+VIN_1") (pintype "passive"))
    )
    (net (code "144") (name "Net-(V401-+VOUT)") (class "Default")
      (node (ref "C401") (pin "1") (pinfunction "1_1") (pintype "passive"))
      (node (ref "F401") (pin "2") (pinfunction "2_2") (pintype "passive"))
      (node (ref "V401") (pin "4") (pinfunction "+VOUT_4") (pintype "passive"))
      (node (ref "V402") (pin "7") (pinfunction "+VOUT_7") (pintype "passive"))
    )
    (net (code "145") (name "Net-(X101-D+)") (class "Default")
      (node (ref "R102") (pin "1") (pinfunction "1_1") (pintype "passive"))
      (node (ref "X101") (pin "3") (pinfunction "D+_3") (pintype "bidirectional"))
    )
    (net (code "146") (name "Net-(X101-D-)") (class "Default")
      (node (ref "R101") (pin "1") (pinfunction "1_1") (pintype "passive"))
      (node (ref "X101") (pin "2") (pinfunction "D-_2") (pintype "bidirectional"))
    )
    (net (code "147") (name "Net-(X103W-A)") (class "Default")
      (node (ref "G101") (pin "+") (pinfunction "+_+") (pintype "passive"))
      (node (ref "R106") (pin "1") (pinfunction "1_1") (pintype "passive"))
      (node (ref "X103") (pin "3") (pinfunction "A_3") (pintype "passive"))
    )
    (net (code "148") (name "Net-(X303AD-A)") (class "Default")
      (node (ref "X303") (pin "5") (pinfunction "A_5") (pintype "passive"))
      (node (ref "X402") (pin "1") (pinfunction "A_1") (pintype "passive"))
      (node (ref "X403") (pin "P$1") (pinfunction "A_P$1") (pintype "passive"))
      (node (ref "X404") (pin "P$4") (pinfunction "4_P$4") (pintype "passive"))
      (node (ref "X405") (pin "P$4") (pinfunction "4_P$4") (pintype "passive"))
    )
    (net (code "149") (name "Net-(X303AE-A)") (class "Default")
      (node (ref "X303") (pin "6") (pinfunction "A_6") (pintype "passive"))
      (node (ref "X402") (pin "2") (pinfunction "A_2") (pintype "passive"))
      (node (ref "X403") (pin "P$2") (pinfunction "A_P$2") (pintype "passive"))
      (node (ref "X404") (pin "P$5") (pinfunction "5_P$5") (pintype "passive"))
      (node (ref "X405") (pin "P$5") (pinfunction "5_P$5") (pintype "passive"))
    )
    (net (code "150") (name "Net-(X303AH-A)") (class "Default")
      (node (ref "ADC0") (pin "1") (pinfunction "1_1") (pintype "passive"))
      (node (ref "R401") (pin "1") (pinfunction "1_1") (pintype "passive"))
      (node (ref "R402") (pin "1") (pinfunction "1_1") (pintype "passive"))
      (node (ref "X303") (pin "9") (pinfunction "A_9") (pintype "passive"))
    )
    (net (code "151") (name "Net-(X303B-A)") (class "Default")
      (node (ref "ADC1") (pin "1") (pinfunction "1_1") (pintype "passive"))
      (node (ref "X303") (pin "10") (pinfunction "A_10") (pintype "passive"))
    )
    (net (code "152") (name "Net-(X303C-A)") (class "Default")
      (node (ref "ADC2") (pin "1") (pinfunction "1_1") (pintype "passive"))
      (node (ref "X303") (pin "11") (pinfunction "A_11") (pintype "passive"))
    )
    (net (code "153") (name "Net-(X303D-A)") (class "Default")
      (node (ref "ADC3") (pin "1") (pinfunction "1_1") (pintype "passive"))
      (node (ref "X303") (pin "12") (pinfunction "A_12") (pintype "passive"))
    )
    (net (code "154") (name "Net-(X303E-A)") (class "Default")
      (node (ref "ADC4") (pin "1") (pinfunction "1_1") (pintype "passive"))
      (node (ref "X303") (pin "13") (pinfunction "A_13") (pintype "passive"))
    )
    (net (code "155") (name "Net-(X303F-A)") (class "Default")
      (node (ref "ADC5") (pin "1") (pinfunction "1_1") (pintype "passive"))
      (node (ref "X303") (pin "14") (pinfunction "A_14") (pintype "passive"))
    )
    (net (code "156") (name "Net-(X303G-A)") (class "Default")
      (node (ref "ADC6") (pin "1") (pinfunction "1_1") (pintype "passive"))
      (node (ref "X303") (pin "15") (pinfunction "A_15") (pintype "passive"))
    )
    (net (code "157") (name "Net-(X303H-A)") (class "Default")
      (node (ref "ADC7") (pin "1") (pinfunction "1_1") (pintype "passive"))
      (node (ref "X303") (pin "16") (pinfunction "A_16") (pintype "passive"))
    )
    (net (code "158") (name "Net-(X303I-A)") (class "Default")
      (node (ref "R403") (pin "1") (pinfunction "1_1") (pintype "passive"))
      (node (ref "X303") (pin "17") (pinfunction "A_17") (pintype "passive"))
    )
    (net (code "159") (name "Net-(X303K-A)") (class "Default")
      (node (ref "R404") (pin "1") (pinfunction "1_1") (pintype "passive"))
      (node (ref "X303") (pin "19") (pinfunction "A_19") (pintype "passive"))
    )
    (net (code "160") (name "Net-(X303N-A)") (class "Default")
      (node (ref "R405") (pin "1") (pinfunction "1_1") (pintype "passive"))
      (node (ref "X303") (pin "21") (pinfunction "A_21") (pintype "passive"))
    )
    (net (code "161") (name "Net-(X303P-A)") (class "Default")
      (node (ref "R406") (pin "1") (pinfunction "1_1") (pintype "passive"))
      (node (ref "X303") (pin "23") (pinfunction "A_23") (pintype "passive"))
    )
    (net (code "162") (name "Net-(X303R-A)") (class "Default")
      (node (ref "R407") (pin "1") (pinfunction "1_1") (pintype "passive"))
      (node (ref "X303") (pin "25") (pinfunction "A_25") (pintype "passive"))
    )
    (net (code "163") (name "Net-(X303T-A)") (class "Default")
      (node (ref "R408") (pin "1") (pinfunction "1_1") (pintype "passive"))
      (node (ref "X303") (pin "27") (pinfunction "A_27") (pintype "passive"))
    )
    (net (code "164") (name "Net-(X303V-A)") (class "Default")
      (node (ref "R409") (pin "1") (pinfunction "1_1") (pintype "passive"))
      (node (ref "X303") (pin "29") (pinfunction "A_29") (pintype "passive"))
    )
    (net (code "165") (name "Net-(X303W-A)") (class "Default")
      (node (ref "D403") (pin "A") (pinfunction "A_A") (pintype "passive"))
      (node (ref "X303") (pin "3") (pinfunction "A_3") (pintype "passive"))
    )
    (net (code "166") (name "Net-(X303Y-A)") (class "Default")
      (node (ref "R410") (pin "1") (pinfunction "1_1") (pintype "passive"))
      (node (ref "X303") (pin "31") (pinfunction "A_31") (pintype "passive"))
    )
    (net (code "167") (name "Net-(X304A-A)") (class "Default")
      (node (ref "R307") (pin "2") (pinfunction "2_2") (pintype "passive"))
      (node (ref "X304") (pin "1") (pinfunction "A_1") (pintype "passive"))
      (node (ref "X308") (pin "P$7") (pinfunction "A_P$7") (pintype "passive"))
    )
    (net (code "168") (name "Net-(X304B-A)") (class "Default")
      (node (ref "R301") (pin "2") (pinfunction "2_2") (pintype "passive"))
      (node (ref "X304") (pin "2") (pinfunction "A_2") (pintype "passive"))
      (node (ref "X308") (pin "P$8") (pinfunction "A_P$8") (pintype "passive"))
    )
    (net (code "169") (name "Net-(X305A-A)") (class "Default")
      (node (ref "R309") (pin "2") (pinfunction "2_2") (pintype "passive"))
      (node (ref "X305") (pin "1") (pinfunction "A_1") (pintype "passive"))
      (node (ref "X308") (pin "P$3") (pinfunction "A_P$3") (pintype "passive"))
    )
    (net (code "170") (name "Net-(X305B-A)") (class "Default")
      (node (ref "R303") (pin "2") (pinfunction "2_2") (pintype "passive"))
      (node (ref "X305") (pin "2") (pinfunction "A_2") (pintype "passive"))
      (node (ref "X308") (pin "P$4") (pinfunction "A_P$4") (pintype "passive"))
    )
    (net (code "171") (name "Net-(X306A-A)") (class "Default")
      (node (ref "R319") (pin "2") (pinfunction "2_2") (pintype "passive"))
      (node (ref "X306") (pin "1") (pinfunction "A_1") (pintype "passive"))
      (node (ref "X308") (pin "P$5") (pinfunction "A_P$5") (pintype "passive"))
    )
    (net (code "172") (name "Net-(X306B-A)") (class "Default")
      (node (ref "R313") (pin "2") (pinfunction "2_2") (pintype "passive"))
      (node (ref "X306") (pin "2") (pinfunction "A_2") (pintype "passive"))
      (node (ref "X308") (pin "P$6") (pinfunction "A_P$6") (pintype "passive"))
    )
    (net (code "173") (name "Net-(X307A-A)") (class "Default")
      (node (ref "R321") (pin "2") (pinfunction "2_2") (pintype "passive"))
      (node (ref "X307") (pin "1") (pinfunction "A_1") (pintype "passive"))
      (node (ref "X308") (pin "P$1") (pinfunction "A_P$1") (pintype "passive"))
    )
    (net (code "174") (name "Net-(X307B-A)") (class "Default")
      (node (ref "R315") (pin "2") (pinfunction "2_2") (pintype "passive"))
      (node (ref "X307") (pin "2") (pinfunction "A_2") (pintype "passive"))
      (node (ref "X308") (pin "P$2") (pinfunction "A_P$2") (pintype "passive"))
    )
    (net (code "175") (name "OUT0") (class "Default")
      (node (ref "D209") (pin "1") (pinfunction "A_1") (pintype "passive"))
      (node (ref "IC101") (pin "51") (pinfunction "(AD0)PA0_51") (pintype "bidirectional"))
      (node (ref "X103") (pin "17") (pinfunction "A_17") (pintype "passive"))
    )
    (net (code "176") (name "OUT1") (class "Default")
      (node (ref "D210") (pin "1") (pinfunction "A_1") (pintype "passive"))
      (node (ref "IC101") (pin "50") (pinfunction "(AD1)PA1_50") (pintype "bidirectional"))
      (node (ref "X103") (pin "19") (pinfunction "A_19") (pintype "passive"))
    )
    (net (code "177") (name "OUT2") (class "Default")
      (node (ref "D211") (pin "1") (pinfunction "A_1") (pintype "passive"))
      (node (ref "IC101") (pin "49") (pinfunction "(AD2)PA2_49") (pintype "bidirectional"))
      (node (ref "X103") (pin "21") (pinfunction "A_21") (pintype "passive"))
    )
    (net (code "178") (name "OUT3") (class "Default")
      (node (ref "D212") (pin "1") (pinfunction "A_1") (pintype "passive"))
      (node (ref "IC101") (pin "48") (pinfunction "(AD3)PA3_48") (pintype "bidirectional"))
      (node (ref "X103") (pin "23") (pinfunction "A_23") (pintype "passive"))
    )
    (net (code "179") (name "OUT4") (class "Default")
      (node (ref "D213") (pin "1") (pinfunction "A_1") (pintype "passive"))
      (node (ref "IC101") (pin "47") (pinfunction "(AD4)PA4_47") (pintype "bidirectional"))
      (node (ref "X103") (pin "25") (pinfunction "A_25") (pintype "passive"))
    )
    (net (code "180") (name "OUT5") (class "Default")
      (node (ref "D214") (pin "1") (pinfunction "A_1") (pintype "passive"))
      (node (ref "IC101") (pin "46") (pinfunction "(AD5)PA5_46") (pintype "bidirectional"))
      (node (ref "X103") (pin "27") (pinfunction "A_27") (pintype "passive"))
    )
    (net (code "181") (name "OUT6") (class "Default")
      (node (ref "D215") (pin "1") (pinfunction "A_1") (pintype "passive"))
      (node (ref "IC101") (pin "45") (pinfunction "(AD6)PA6_45") (pintype "bidirectional"))
      (node (ref "X103") (pin "29") (pinfunction "A_29") (pintype "passive"))
    )
    (net (code "182") (name "OUT7") (class "Default")
      (node (ref "D216") (pin "1") (pinfunction "A_1") (pintype "passive"))
      (node (ref "IC101") (pin "44") (pinfunction "(AD7)PA7_44") (pintype "bidirectional"))
      (node (ref "X103") (pin "31") (pinfunction "A_31") (pintype "passive"))
    )
    (net (code "183") (name "RE") (class "Default")
      (node (ref "IC101") (pin "30") (pinfunction "(XCK1)PD5_30") (pintype "bidirectional"))
      (node (ref "IC102") (pin "2") (pinfunction "RE/_2") (pintype "input"))
    )
    (net (code "184") (name "RXD") (class "Default")
      (node (ref "IC101") (pin "27") (pinfunction "(RXD1/INT2)PD2_27") (pintype "bidirectional"))
      (node (ref "IC102") (pin "1") (pinfunction "RO_1") (pintype "output"))
    )
    (net (code "185") (name "SCK") (class "Default")
      (node (ref "IC101") (pin "11") (pinfunction "(PCINT1/SCLK)PB1_11") (pintype "bidirectional"))
      (node (ref "X102") (pin "SCK") (pinfunction "SCK_SCK") (pintype "passive"))
    )
    (net (code "186") (name "TE") (class "Default")
      (node (ref "IC101") (pin "29") (pinfunction "(ICP1)PD4_29") (pintype "bidirectional"))
      (node (ref "IC102") (pin "3") (pinfunction "DE_3") (pintype "input"))
    )
    (net (code "187") (name "TXD") (class "Default")
      (node (ref "IC101") (pin "28") (pinfunction "(TXD1/INT3)PD3_28") (pintype "bidirectional"))
      (node (ref "IC102") (pin "4") (pinfunction "DI_4") (pintype "input"))
    )
    (net (code "188") (name "V+") (class "Default")
      (node (ref "D401") (pin "A") (pinfunction "A_A") (pintype "passive"))
      (node (ref "X401") (pin "1") (pinfunction "A_1") (pintype "passive"))
      (node (ref "X403") (pin "P$3") (pinfunction "A_P$3") (pintype "passive"))
      (node (ref "X404") (pin "P$1") (pinfunction "1_P$1") (pintype "passive"))
      (node (ref "X404") (pin "P$2") (pinfunction "2_P$2") (pintype "passive"))
      (node (ref "X405") (pin "P$1") (pinfunction "1_P$1") (pintype "passive"))
      (node (ref "X405") (pin "P$2") (pinfunction "2_P$2") (pintype "passive"))
    )
    (net (code "189") (name "V-") (class "Default")
      (node (ref "V401") (pin "1") (pinfunction "-VIN_1") (pintype "passive"))
      (node (ref "V402") (pin "2") (pinfunction "-VIN_2") (pintype "passive"))
      (node (ref "X401") (pin "2") (pinfunction "A_2") (pintype "passive"))
      (node (ref "X403") (pin "P$4") (pinfunction "A_P$4") (pintype "passive"))
      (node (ref "X404") (pin "P$7") (pinfunction "7_P$7") (pintype "passive"))
      (node (ref "X404") (pin "P$8") (pinfunction "8_P$8") (pintype "passive"))
      (node (ref "X405") (pin "P$7") (pinfunction "7_P$7") (pintype "passive"))
      (node (ref "X405") (pin "P$8") (pinfunction "8_P$8") (pintype "passive"))
    )
    (net (code "190") (name "unconnected-(IC101-(INT.5{slash}TOSC2)PE5-Pad19)") (class "Default")
      (node (ref "IC101") (pin "19") (pinfunction "(INT.5/TOSC2)PE5_19") (pintype "bidirectional"))
    )
    (net (code "191") (name "unconnected-(IC101-(PCINT0{slash}SS)PB0-Pad10)") (class "Default")
      (node (ref "IC101") (pin "10") (pinfunction "(PCINT0/SS)PB0_10") (pintype "bidirectional"))
    )
    (net (code "192") (name "unconnected-(IC101-(PCINT4{slash}OC.2A)PB4-Pad14)") (class "Default")
      (node (ref "IC101") (pin "14") (pinfunction "(PCINT4/OC.2A)PB4_14") (pintype "bidirectional"))
    )
    (net (code "193") (name "unconnected-(IC401A-SQW{slash}~{INTB}-Pad7)") (class "Default")
      (node (ref "IC401") (pin "7") (pinfunction "SQW/~{INTB}_7") (pintype "open_collector"))
    )
    (net (code "194") (name "unconnected-(IC401A-~{INTA}-Pad3)") (class "Default")
      (node (ref "IC401") (pin "3") (pinfunction "~{INTA}_3") (pintype "open_collector"))
    )
    (net (code "195") (name "unconnected-(IC402A-WC-Pad7)") (class "Default")
      (node (ref "IC402") (pin "7") (pinfunction "WC_7") (pintype "input"))
    )
    (net (code "196") (name "unconnected-(R108-8-Pad4B)") (class "Default")
      (node (ref "R108") (pin "4B") (pinfunction "8_4B") (pintype "passive"))
    )
    (net (code "197") (name "unconnected-(X404-3-PadP$3)") (class "Default")
      (node (ref "X404") (pin "P$3") (pinfunction "3_P$3") (pintype "passive"))
    )
    (net (code "198") (name "unconnected-(X404-6-PadP$6)") (class "Default")
      (node (ref "X404") (pin "P$6") (pinfunction "6_P$6") (pintype "passive"))
    )
    (net (code "199") (name "unconnected-(X405-3-PadP$3)") (class "Default")
      (node (ref "X405") (pin "P$3") (pinfunction "3_P$3") (pintype "passive"))
    )
    (net (code "200") (name "unconnected-(X405-6-PadP$6)") (class "Default")
      (node (ref "X405") (pin "P$6") (pinfunction "6_P$6") (pintype "passive"))
    )
    (net (code "201") (name "~{RESET}") (class "Default")
      (node (ref "IC101") (pin "20") (pinfunction "RESET_20") (pintype "input"))
      (node (ref "R103") (pin "1") (pinfunction "1_1") (pintype "passive"))
      (node (ref "X102") (pin "RESET") (pinfunction "RESET_RESET") (pintype "passive"))
    )
    (net (code "202") (name "~{R}") (class "Default")
      (node (ref "IC101") (pin "33") (pinfunction "(WR)PE0_33") (pintype "bidirectional"))
      (node (ref "IC103") (pin "9") (pinfunction "~{CLR}_9") (pintype "input"))
    )
  )
)
